# main_board.net
KiCad netlist of a schematic drawn in EAGLE
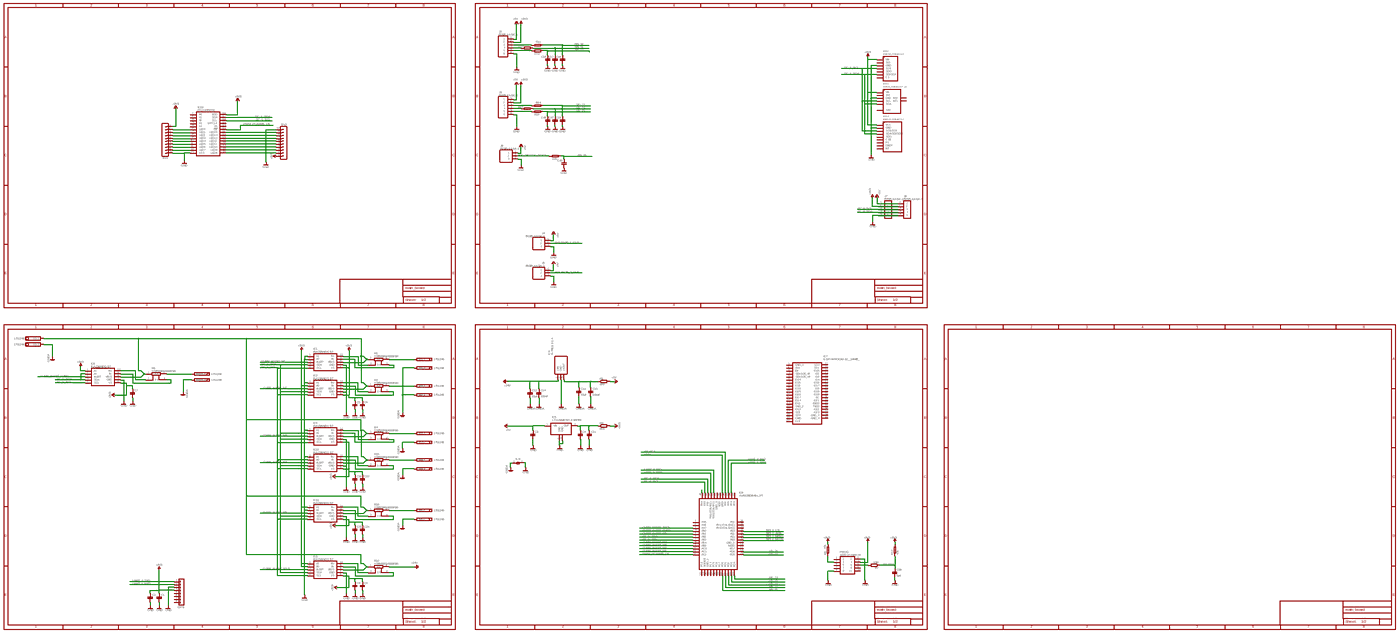
[diagram p0: schematic, sheet 1, overview]
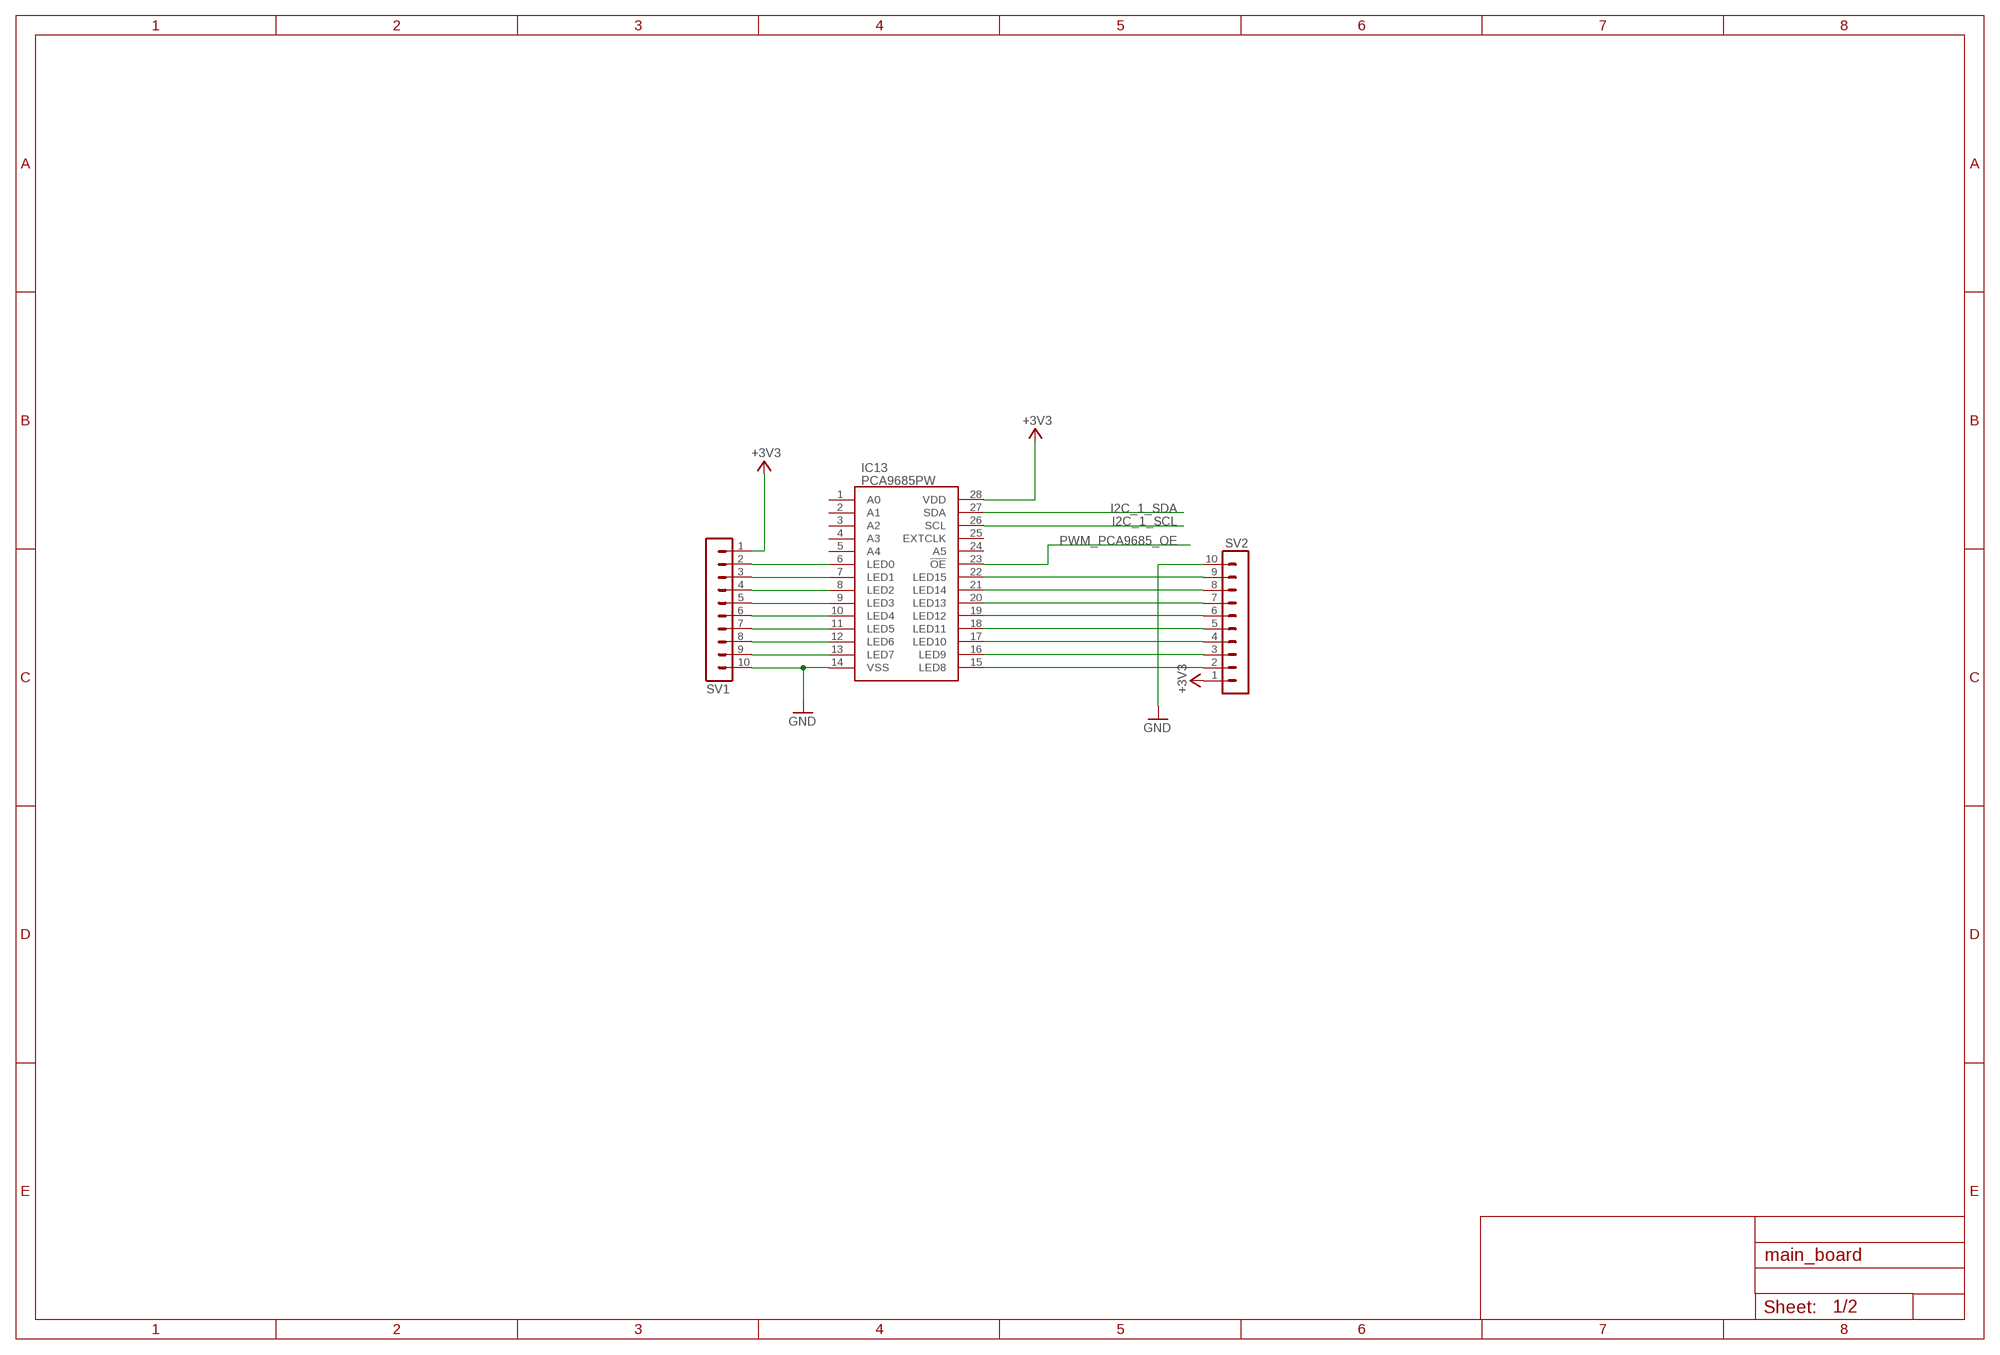
[diagram p1: schematic, sheet 1, part 1 of 7]
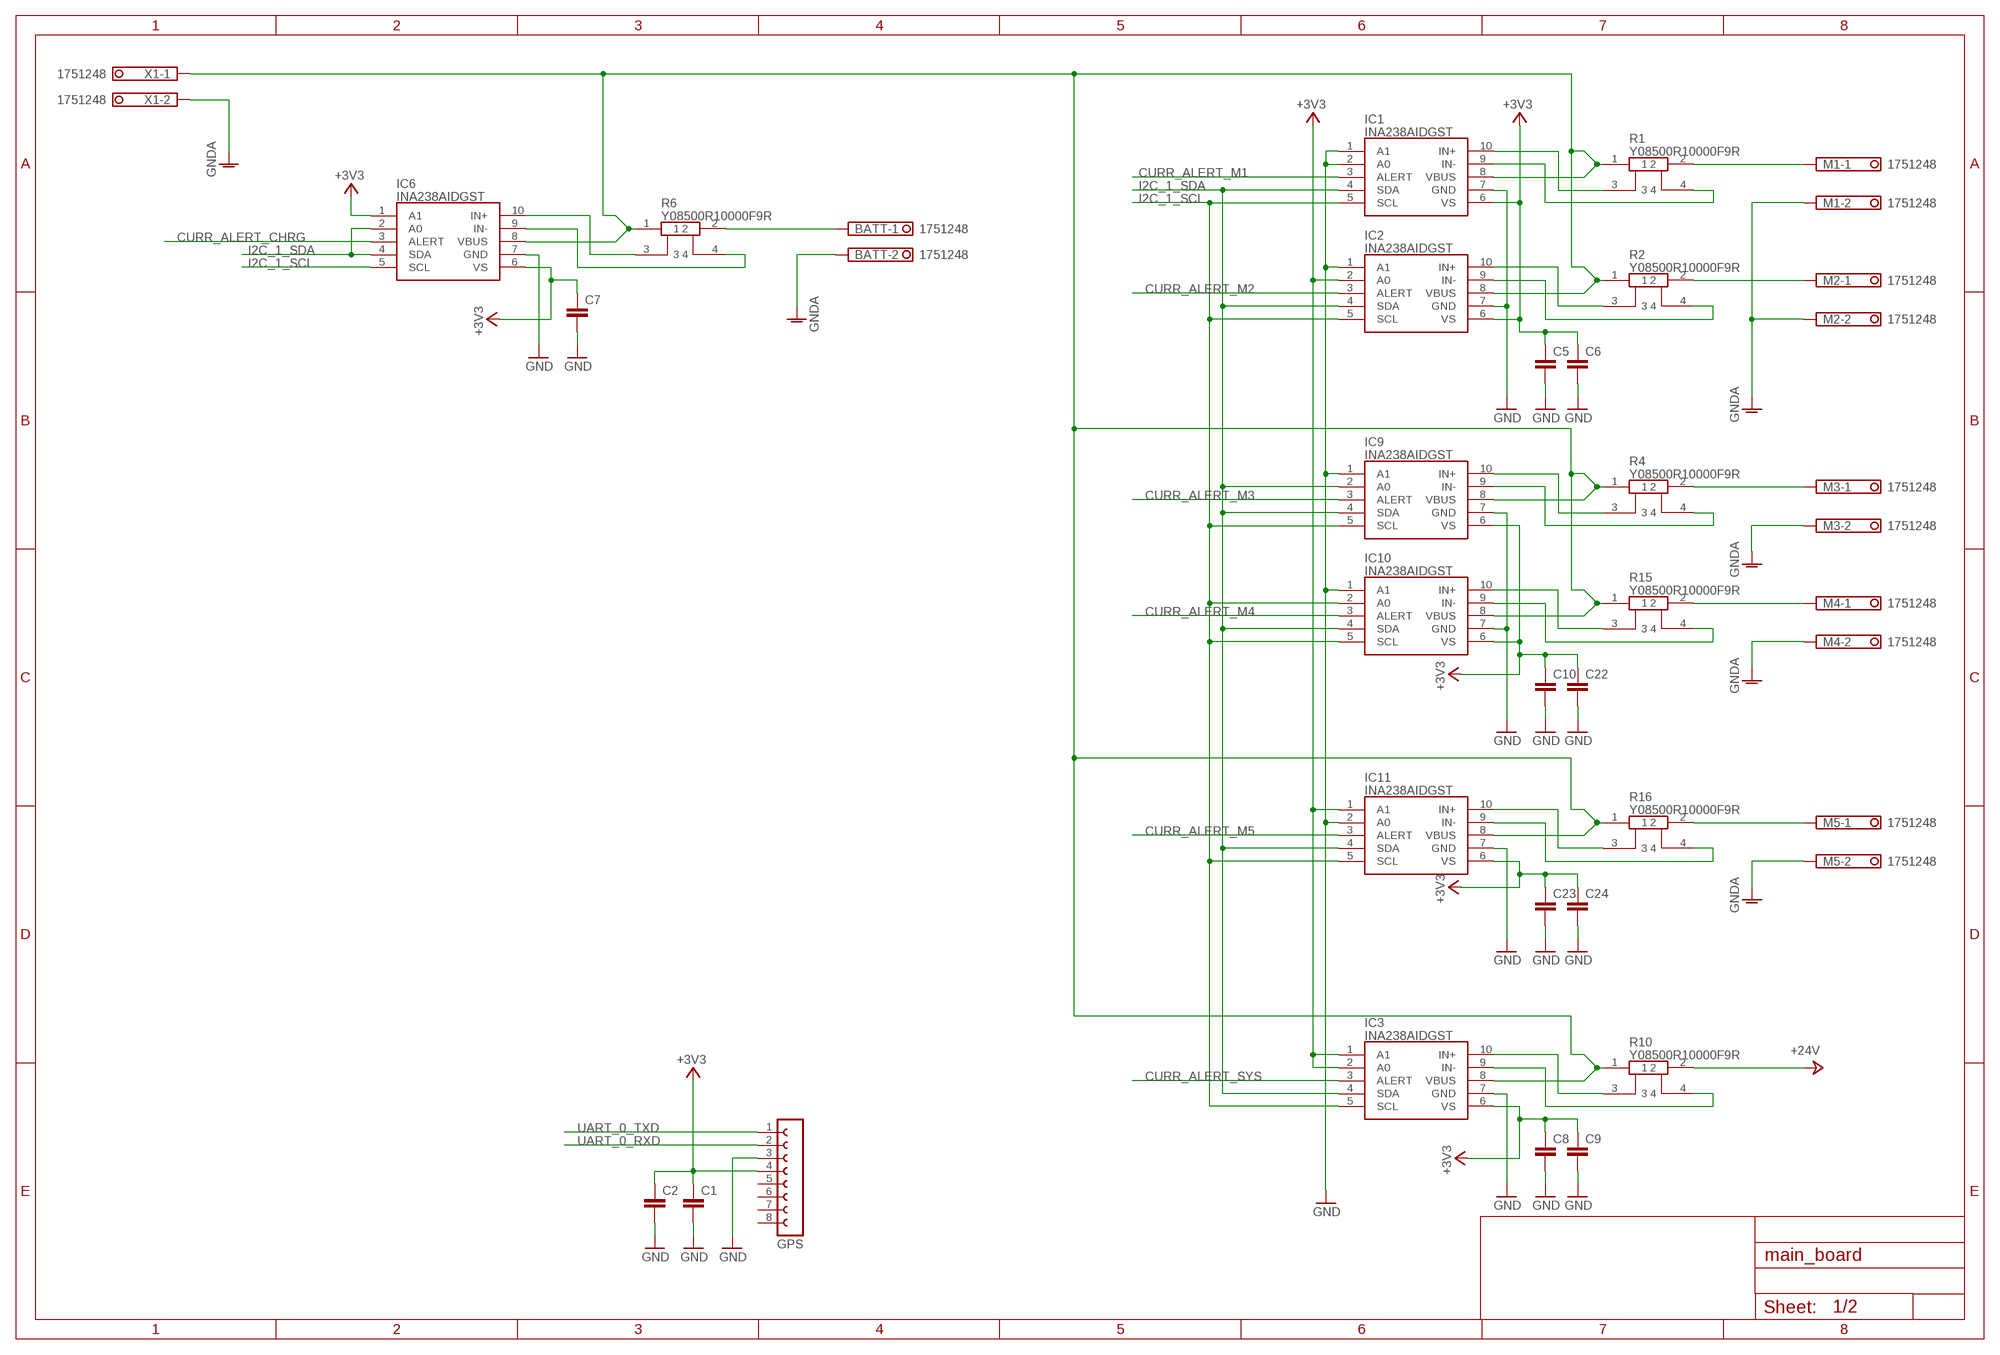
[diagram p2: schematic, sheet 1, part 2 of 7]
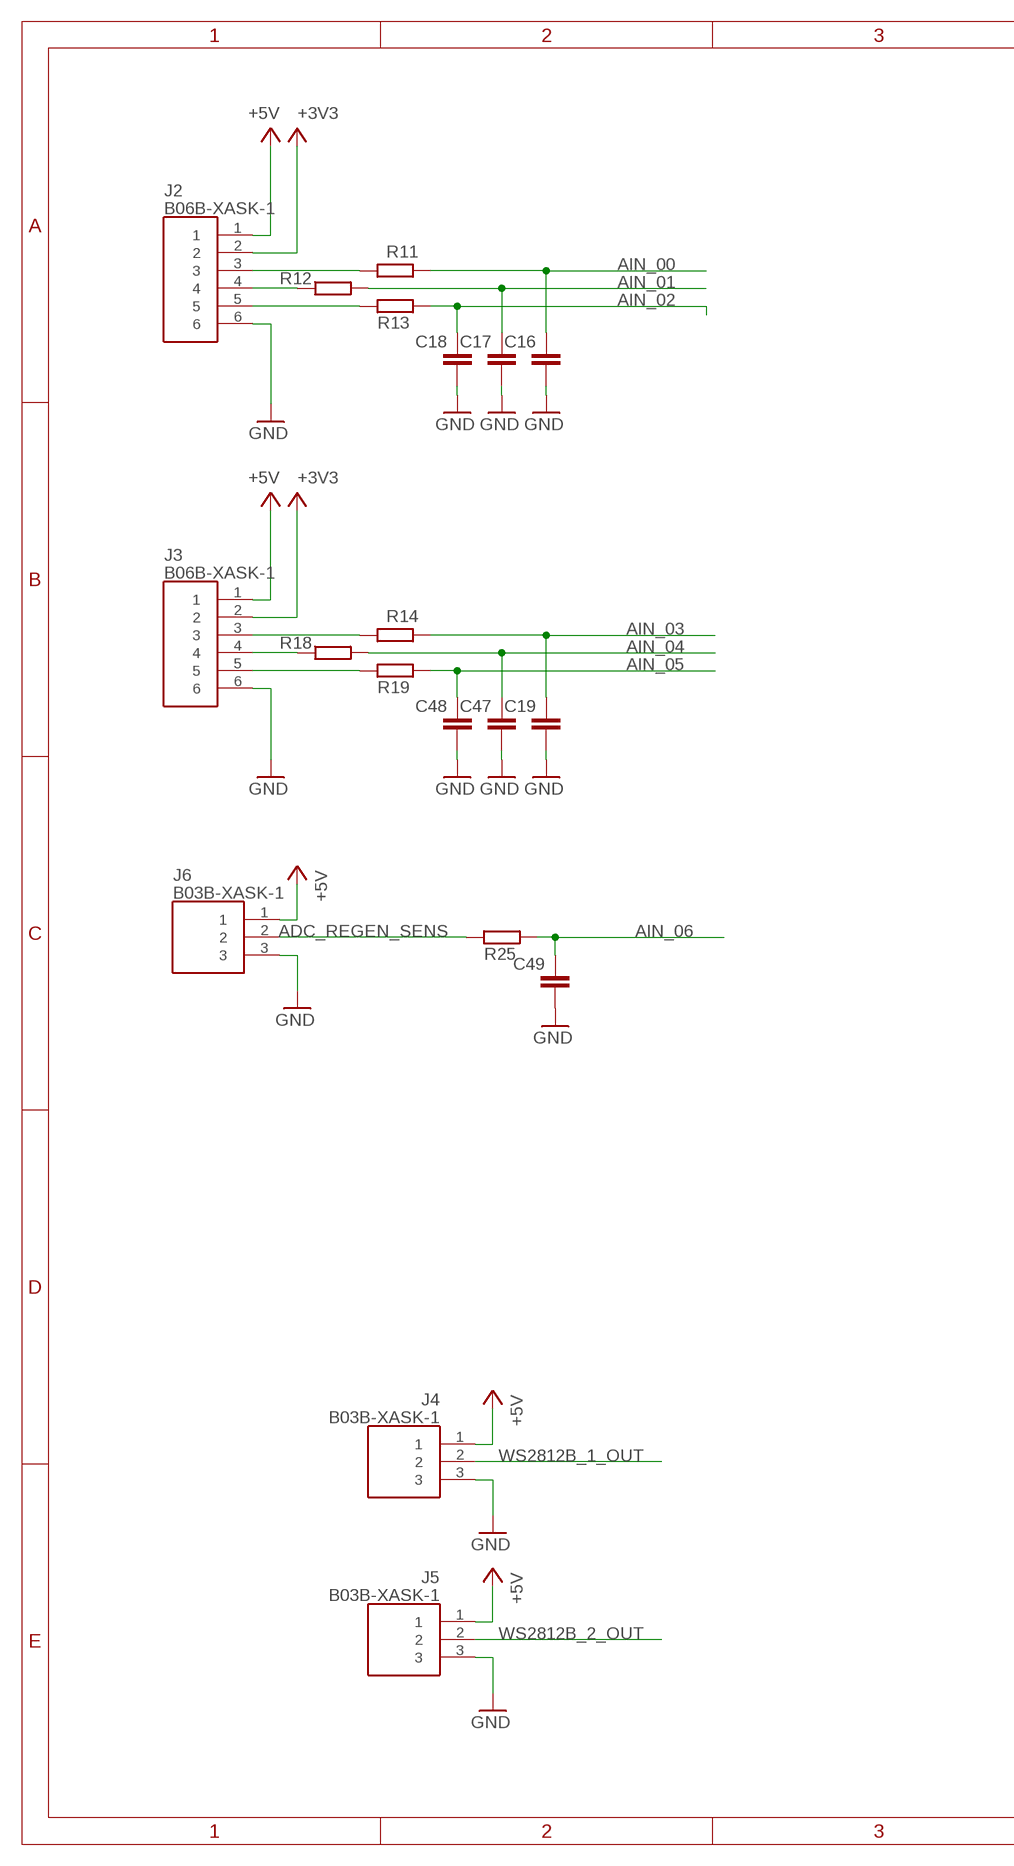
[diagram p3: schematic, sheet 1, part 3 of 7]
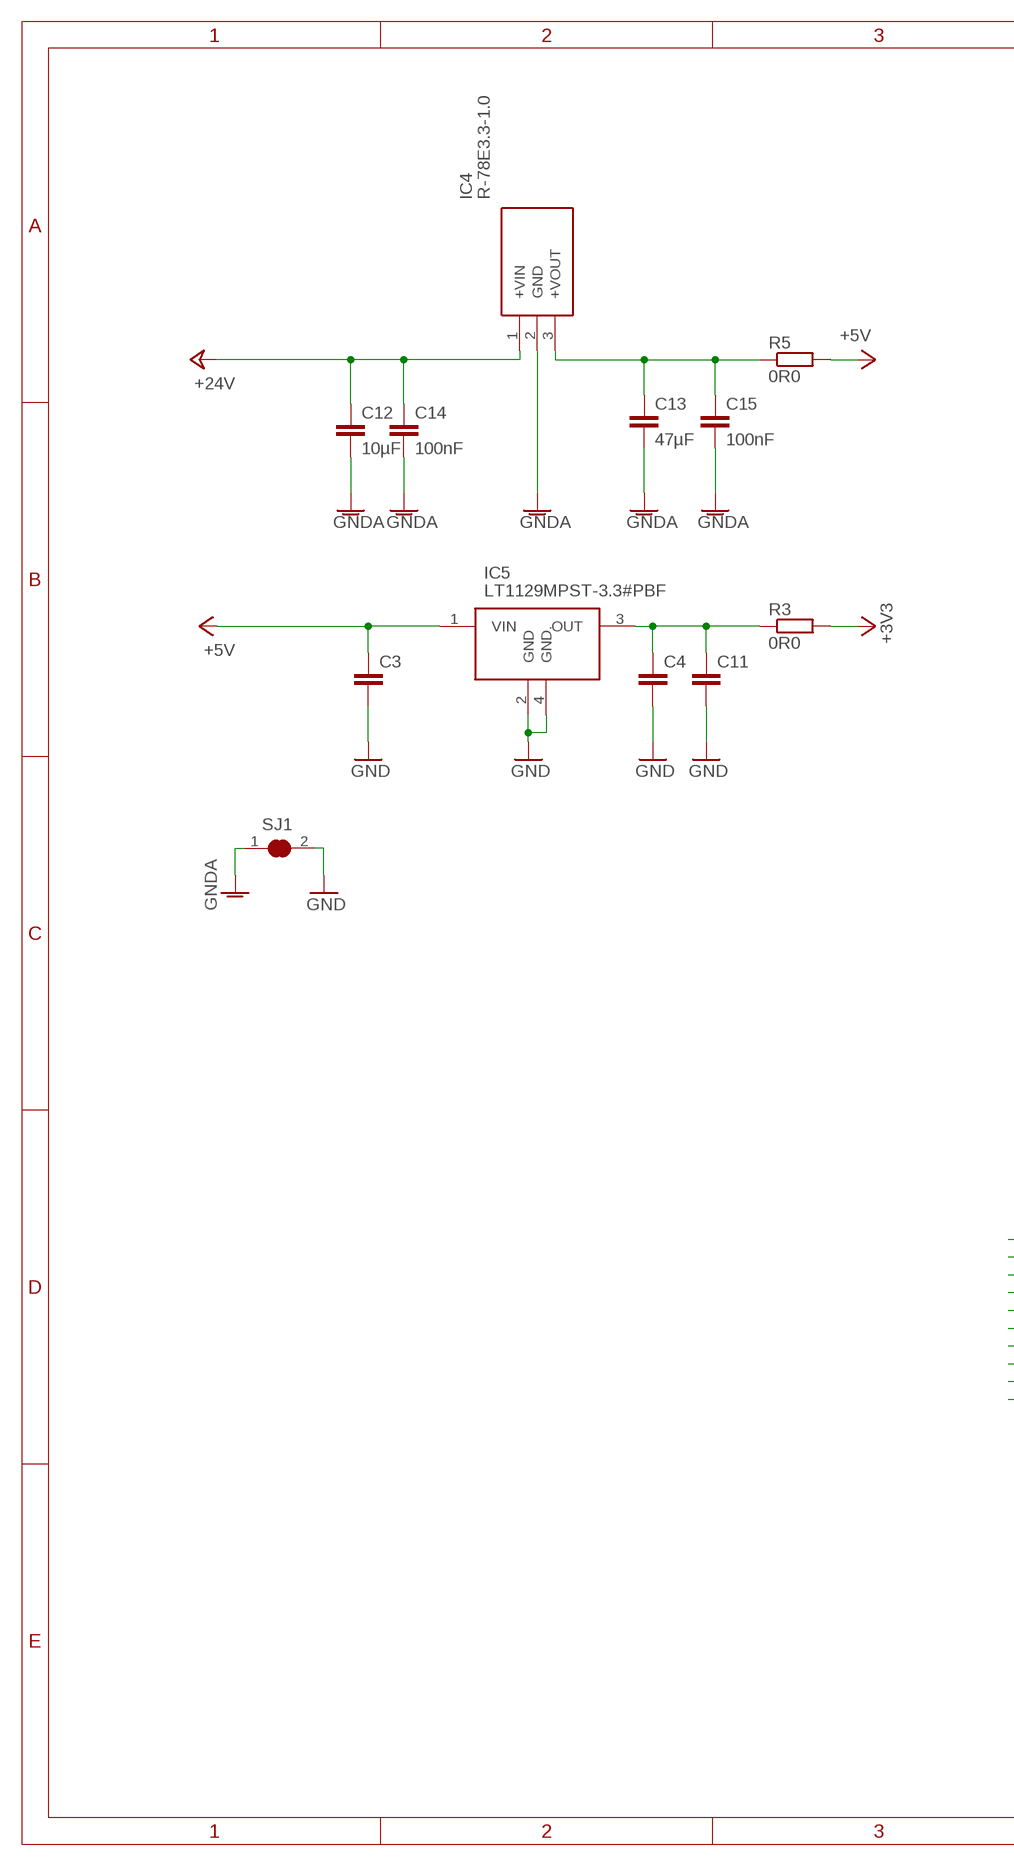
[diagram p4: schematic, sheet 1, part 4 of 7]
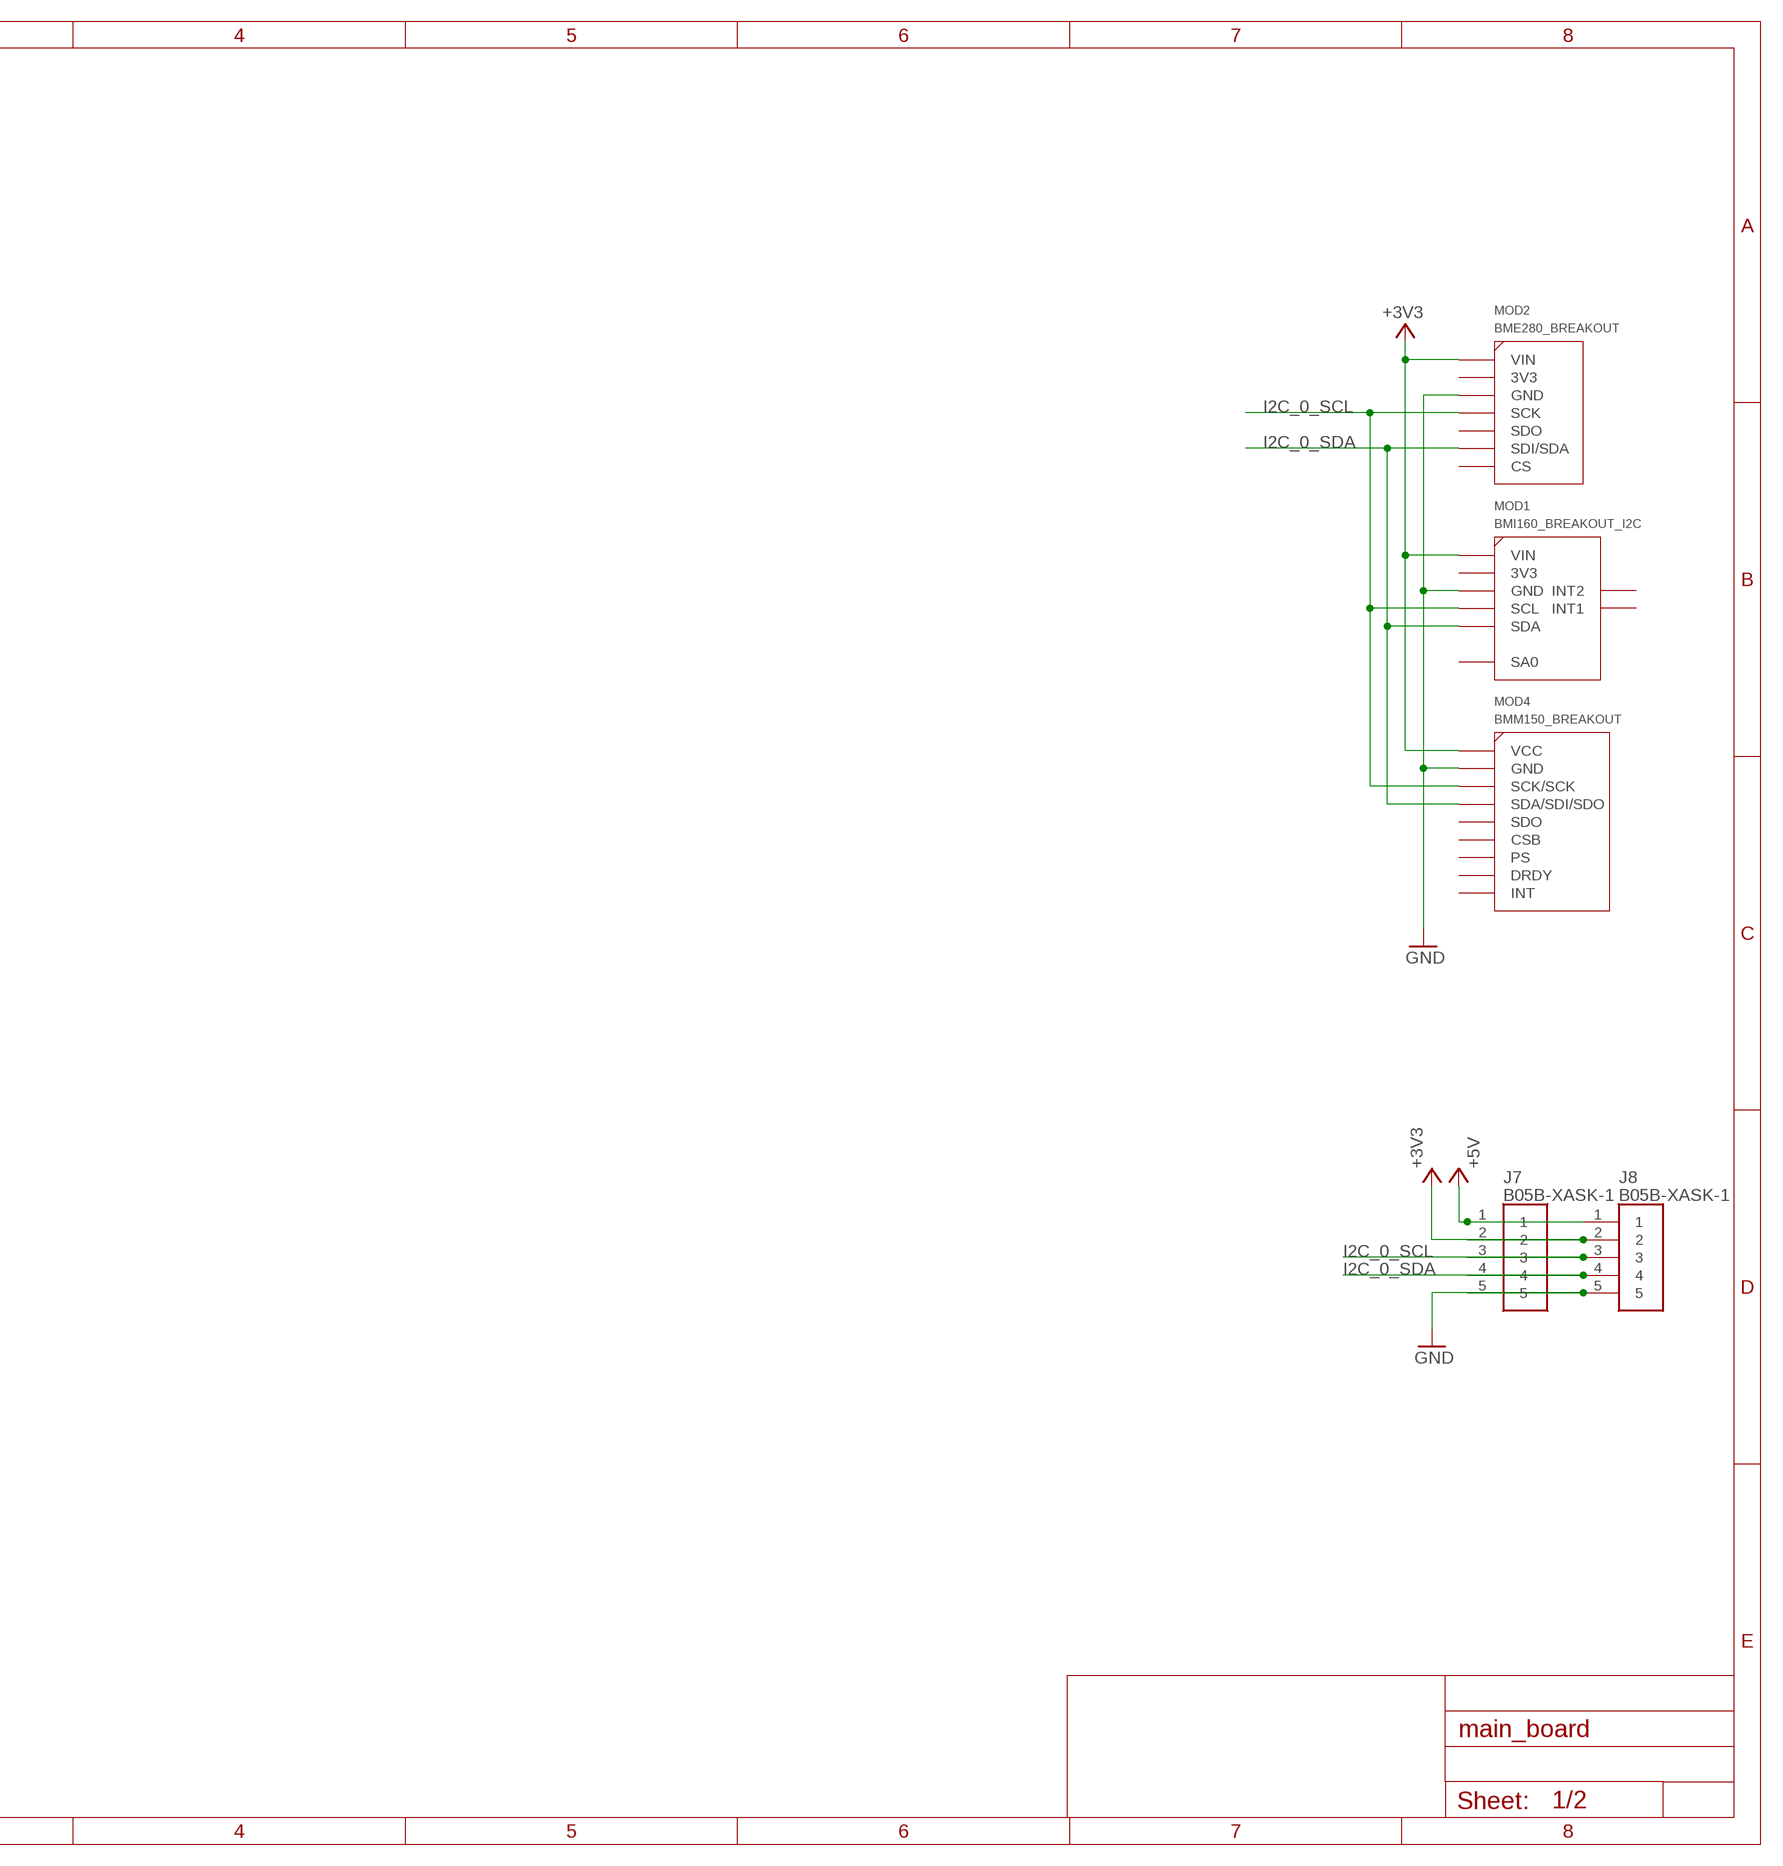
[diagram p5: schematic, sheet 1, part 5 of 7]
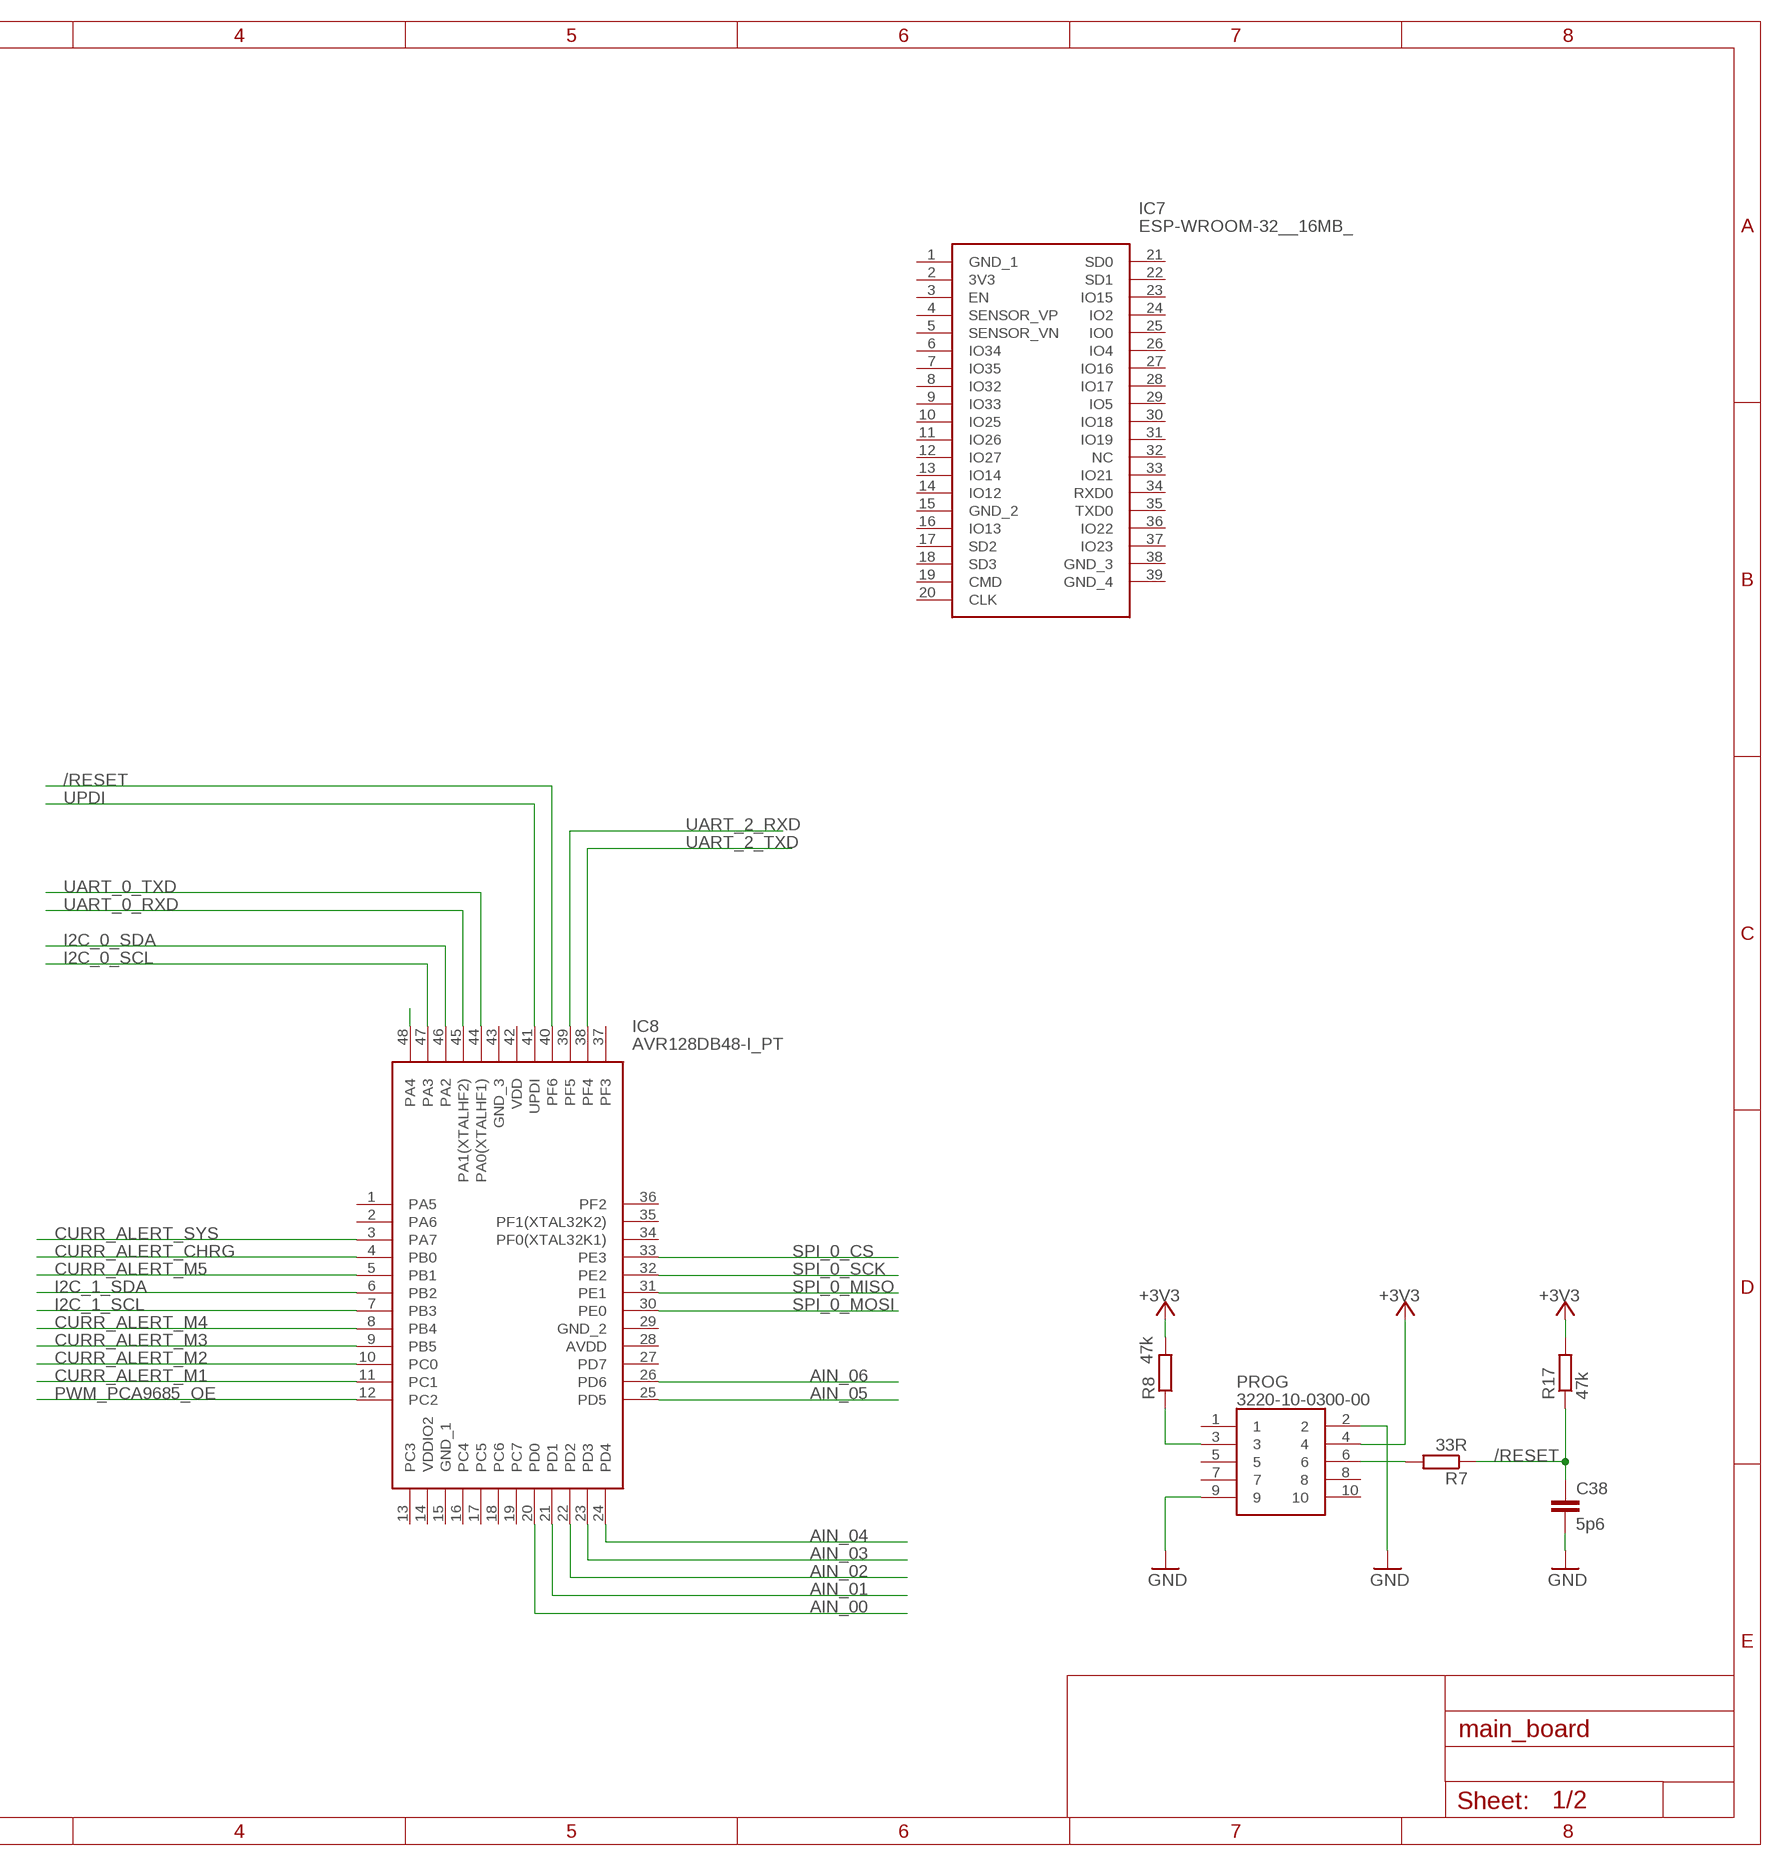
[diagram p6: schematic, sheet 1, part 6 of 7]
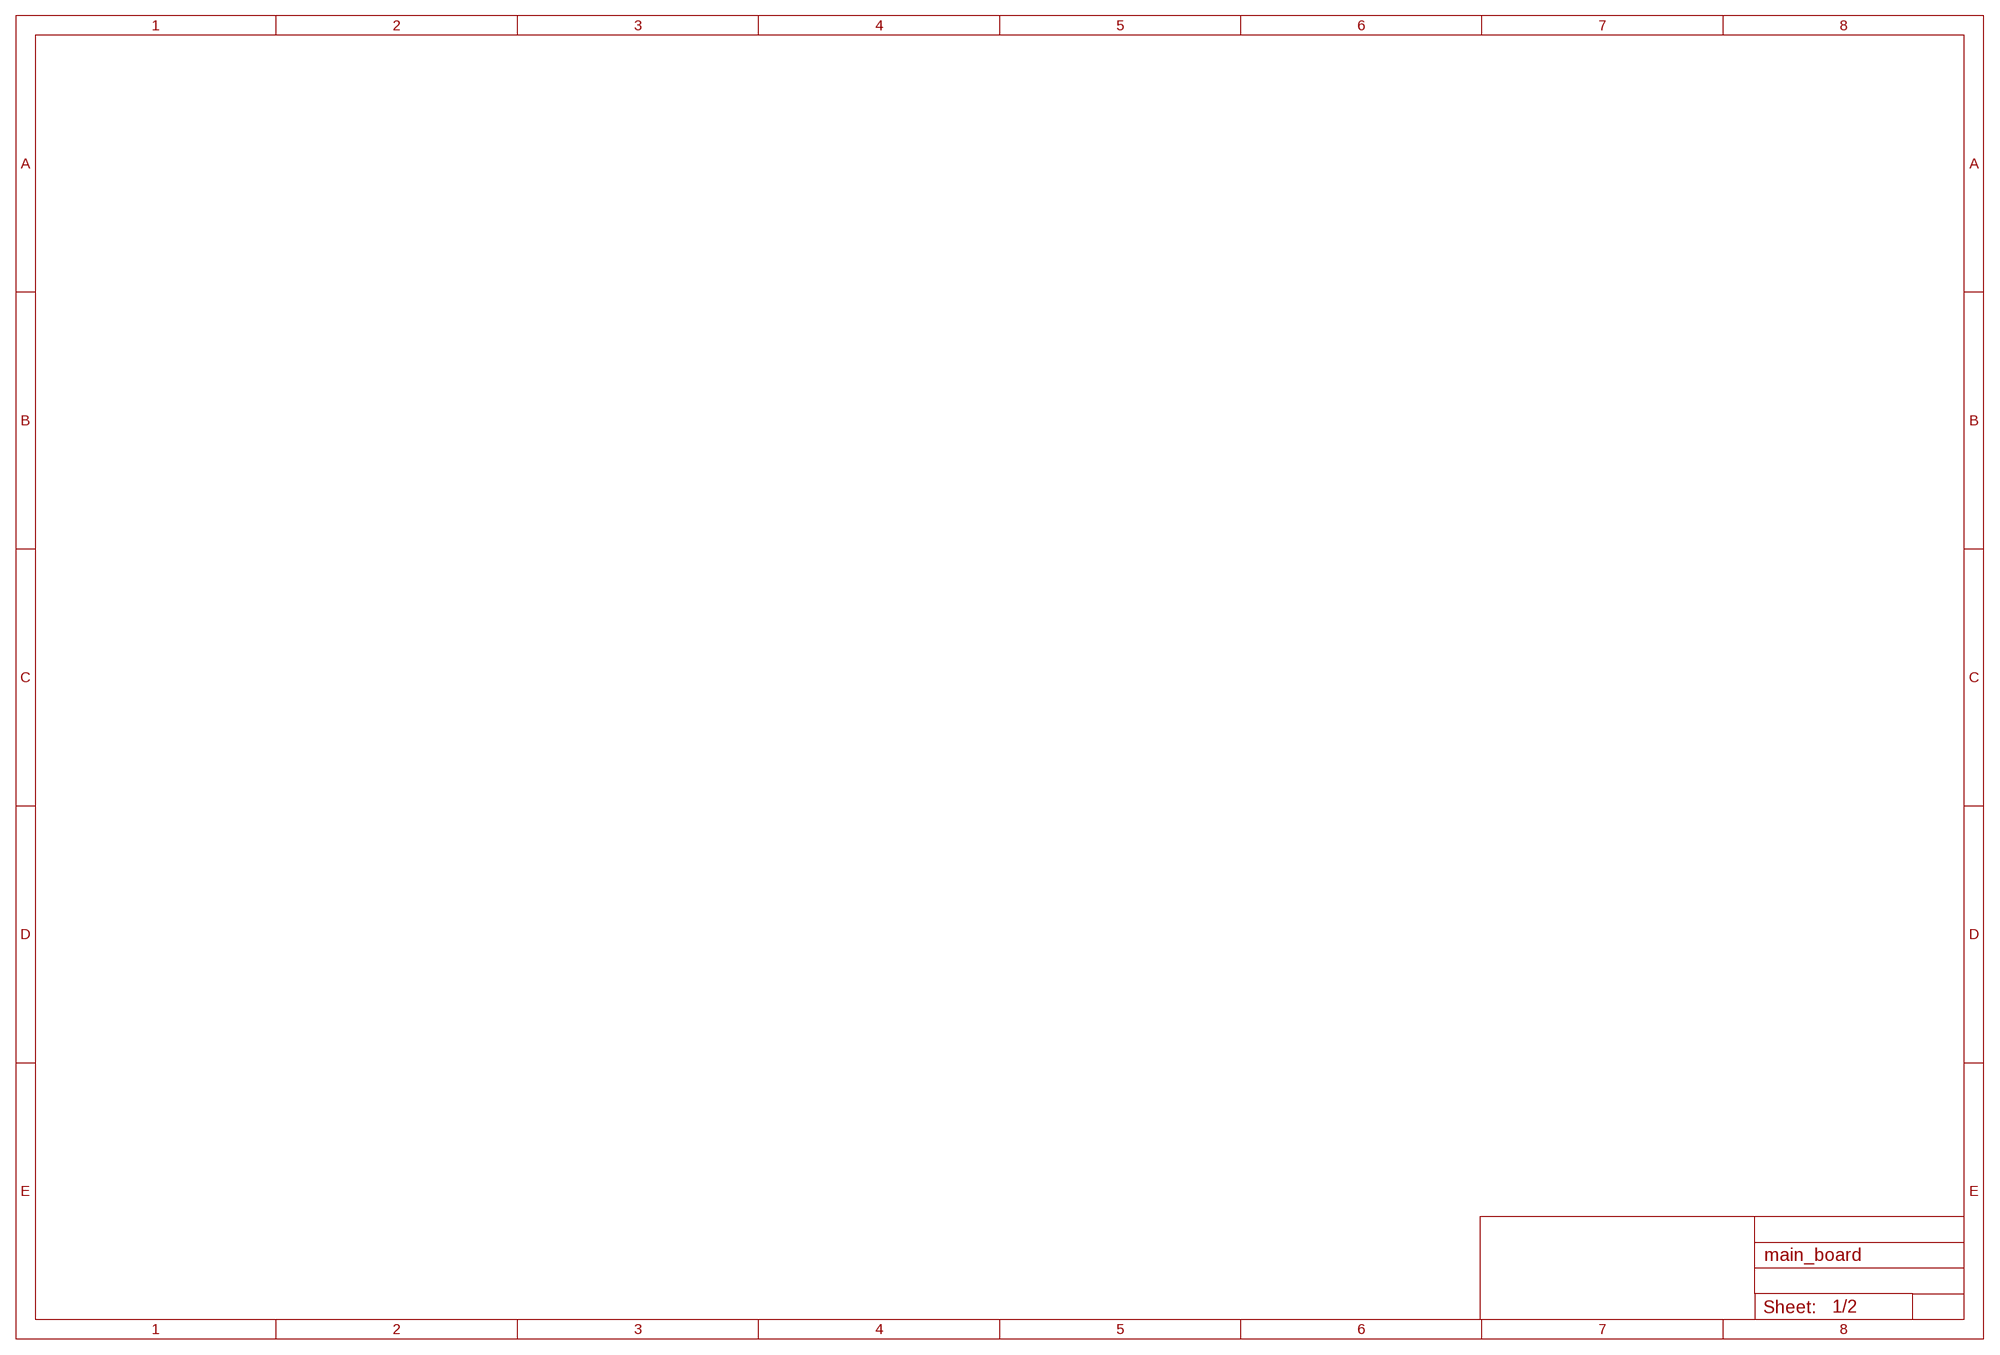
[diagram p7: schematic, sheet 1, part 7 of 7]
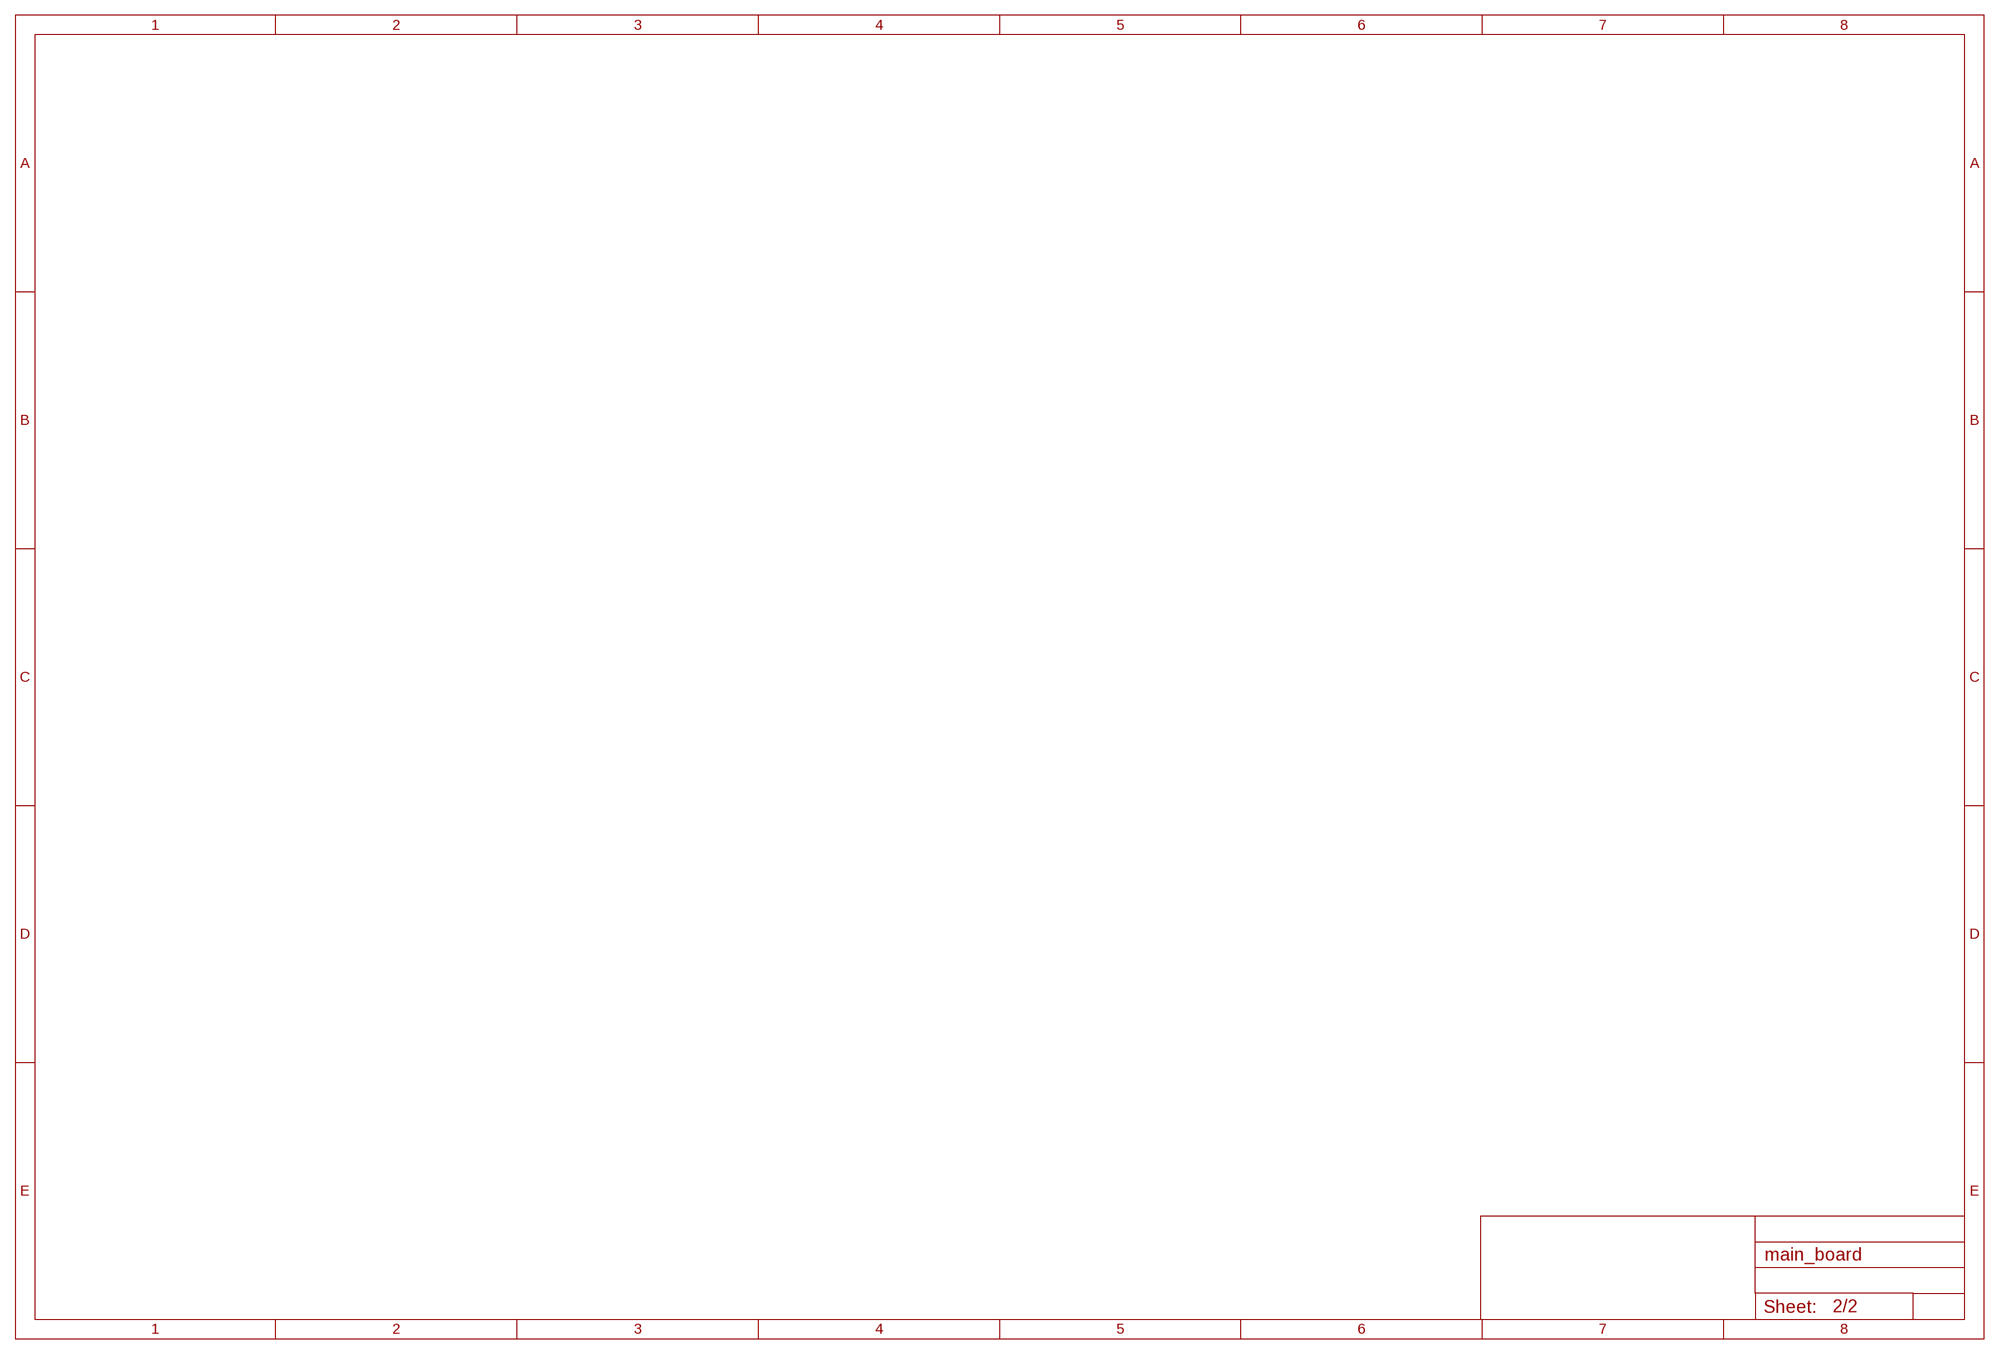
[diagram p8: schematic, sheet 2]

(export (version "E")
  (design (tool "Eeschema 10.0.6"))
  (components
    (comp (ref "BATT")
      (value "1751248")
      (footprint "eagle-import:1751248")
      (libsource (lib "eagle-import") (part "1751248"))
    )
    (comp (ref "C1")
      (value "C-EUC0603")
      (footprint "eagle-import:C0603")
      (libsource (lib "eagle-import") (part "C-EUC0603"))
    )
    (comp (ref "C2")
      (value "C-EUC0603")
      (footprint "eagle-import:C0603")
      (libsource (lib "eagle-import") (part "C-EUC0603"))
    )
    (comp (ref "C3")
      (value "C-EUC0603")
      (footprint "eagle-import:C0603")
      (libsource (lib "eagle-import") (part "C-EUC0603"))
    )
    (comp (ref "C4")
      (value "C-EUC0603")
      (footprint "eagle-import:C0603")
      (libsource (lib "eagle-import") (part "C-EUC0603"))
    )
    (comp (ref "C5")
      (value "C-EUC0603")
      (footprint "eagle-import:C0603")
      (libsource (lib "eagle-import") (part "C-EUC0603"))
    )
    (comp (ref "C6")
      (value "C-EUC0603")
      (footprint "eagle-import:C0603")
      (libsource (lib "eagle-import") (part "C-EUC0603"))
    )
    (comp (ref "C7")
      (value "C-EUC0603")
      (footprint "eagle-import:C0603")
      (libsource (lib "eagle-import") (part "C-EUC0603"))
    )
    (comp (ref "C8")
      (value "C-EUC0603")
      (footprint "eagle-import:C0603")
      (libsource (lib "eagle-import") (part "C-EUC0603"))
    )
    (comp (ref "C9")
      (value "C-EUC0603")
      (footprint "eagle-import:C0603")
      (libsource (lib "eagle-import") (part "C-EUC0603"))
    )
    (comp (ref "C10")
      (value "C-EUC0603")
      (footprint "eagle-import:C0603")
      (libsource (lib "eagle-import") (part "C-EUC0603"))
    )
    (comp (ref "C11")
      (value "C-EUC0603")
      (footprint "eagle-import:C0603")
      (libsource (lib "eagle-import") (part "C-EUC0603"))
    )
    (comp (ref "C12")
      (value "10µF")
      (footprint "eagle-import:C1210")
      (libsource (lib "eagle-import") (part "C-EUC1210"))
    )
    (comp (ref "C13")
      (value "47µF")
      (footprint "eagle-import:C1210")
      (libsource (lib "eagle-import") (part "C-EUC1210"))
    )
    (comp (ref "C14")
      (value "100nF")
      (footprint "eagle-import:C0603")
      (libsource (lib "eagle-import") (part "C-EUC0603"))
    )
    (comp (ref "C15")
      (value "100nF")
      (footprint "eagle-import:C0603")
      (libsource (lib "eagle-import") (part "C-EUC0603"))
    )
    (comp (ref "C16")
      (value "C-EUC0603")
      (footprint "eagle-import:C0603")
      (libsource (lib "eagle-import") (part "C-EUC0603"))
    )
    (comp (ref "C17")
      (value "C-EUC0603")
      (footprint "eagle-import:C0603")
      (libsource (lib "eagle-import") (part "C-EUC0603"))
    )
    (comp (ref "C18")
      (value "C-EUC0603")
      (footprint "eagle-import:C0603")
      (libsource (lib "eagle-import") (part "C-EUC0603"))
    )
    (comp (ref "C19")
      (value "C-EUC0603")
      (footprint "eagle-import:C0603")
      (libsource (lib "eagle-import") (part "C-EUC0603"))
    )
    (comp (ref "C22")
      (value "C-EUC0603")
      (footprint "eagle-import:C0603")
      (libsource (lib "eagle-import") (part "C-EUC0603"))
    )
    (comp (ref "C23")
      (value "C-EUC0603")
      (footprint "eagle-import:C0603")
      (libsource (lib "eagle-import") (part "C-EUC0603"))
    )
    (comp (ref "C24")
      (value "C-EUC0603")
      (footprint "eagle-import:C0603")
      (libsource (lib "eagle-import") (part "C-EUC0603"))
    )
    (comp (ref "C38")
      (value "5p6")
      (footprint "eagle-import:C0603")
      (libsource (lib "eagle-import") (part "C-EUC0603"))
    )
    (comp (ref "C47")
      (value "C-EUC0603")
      (footprint "eagle-import:C0603")
      (libsource (lib "eagle-import") (part "C-EUC0603"))
    )
    (comp (ref "C48")
      (value "C-EUC0603")
      (footprint "eagle-import:C0603")
      (libsource (lib "eagle-import") (part "C-EUC0603"))
    )
    (comp (ref "C49")
      (value "C-EUC0603")
      (footprint "eagle-import:C0603")
      (libsource (lib "eagle-import") (part "C-EUC0603"))
    )
    (comp (ref "GPS")
      (value "FE08-1")
      (footprint "eagle-import:FE08")
      (libsource (lib "eagle-import") (part "FE08-1"))
    )
    (comp (ref "IC1")
      (value "INA238AIDGST")
      (footprint "eagle-import:SOP50P490X110-10N")
      (fields (field (name "MOUSER_PART_NUMBER") "595-INA238AIDGST"))
      (libsource (lib "eagle-import") (part "INA238AIDGST"))
    )
    (comp (ref "IC2")
      (value "INA238AIDGST")
      (footprint "eagle-import:SOP50P490X110-10N")
      (fields (field (name "MOUSER_PART_NUMBER") "595-INA238AIDGST"))
      (libsource (lib "eagle-import") (part "INA238AIDGST"))
    )
    (comp (ref "IC3")
      (value "INA238AIDGST")
      (footprint "eagle-import:SOP50P490X110-10N")
      (fields (field (name "MOUSER_PART_NUMBER") "595-INA238AIDGST"))
      (libsource (lib "eagle-import") (part "INA238AIDGST"))
    )
    (comp (ref "IC4")
      (value "R-78E3.3-1.0")
      (footprint "eagle-import:R78E3310")
      (fields (field (name "MOUSER_PART_NUMBER") "919-R-78E3.3-1.0"))
      (libsource (lib "eagle-import") (part "R-78E3.3-1.0"))
    )
    (comp (ref "IC5")
      (value "LT1129MPST-3.3#PBF")
      (footprint "eagle-import:SOT230P700X180-4N")
      (fields (field (name "MOUSER_PART_NUMBER") "584-1129MPST-3.3PBF"))
      (libsource (lib "eagle-import") (part "LT1129MPST-3.3#PBF"))
    )
    (comp (ref "IC6")
      (value "INA238AIDGST")
      (footprint "eagle-import:SOP50P490X110-10N")
      (fields (field (name "MOUSER_PART_NUMBER") "595-INA238AIDGST"))
      (libsource (lib "eagle-import") (part "INA238AIDGST"))
    )
    (comp (ref "IC7")
      (value "ESP-WROOM-32__16MB_")
      (footprint "eagle-import:ESP32WROOM32D")
      (fields
        (field (name "ARROW_PART_NUMBER") "ESP-WROOM-32 (16MB)")
        (field (name "MOUSER_PART_NUMBER") "356-ESPWROOM3216MB")
      )
      (libsource (lib "eagle-import") (part "ESP-WROOM-32__16MB_"))
    )
    (comp (ref "IC8")
      (value "AVR128DB48-I_PT")
      (footprint "eagle-import:QFP50P900X900X120-48N")
      (fields
        (field (name "ARROW_PART_NUMBER") "AVR128DB48-I/PT")
        (field (name "MOUSER_PART_NUMBER") "579-AVR128DB48-I/PT")
      )
      (libsource (lib "eagle-import") (part "AVR128DB48-I_PT"))
    )
    (comp (ref "IC9")
      (value "INA238AIDGST")
      (footprint "eagle-import:SOP50P490X110-10N")
      (fields (field (name "MOUSER_PART_NUMBER") "595-INA238AIDGST"))
      (libsource (lib "eagle-import") (part "INA238AIDGST"))
    )
    (comp (ref "IC10")
      (value "INA238AIDGST")
      (footprint "eagle-import:SOP50P490X110-10N")
      (fields (field (name "MOUSER_PART_NUMBER") "595-INA238AIDGST"))
      (libsource (lib "eagle-import") (part "INA238AIDGST"))
    )
    (comp (ref "IC11")
      (value "INA238AIDGST")
      (footprint "eagle-import:SOP50P490X110-10N")
      (fields (field (name "MOUSER_PART_NUMBER") "595-INA238AIDGST"))
      (libsource (lib "eagle-import") (part "INA238AIDGST"))
    )
    (comp (ref "IC13")
      (value "PCA9685PW")
      (footprint "eagle-import:SOP65P640X110-28N")
      (libsource (lib "eagle-import") (part "PCA9685PW"))
    )
    (comp (ref "J2")
      (value "B06B-XASK-1")
      (footprint "eagle-import:SHDR6W60P0X250_1X6_1750X640X88")
      (fields (field (name "ARROW_PART_NUMBER") "B06B-XASK-1 (LF)(SN)"))
      (libsource (lib "eagle-import") (part "B06B-XASK-1"))
    )
    (comp (ref "J3")
      (value "B06B-XASK-1")
      (footprint "eagle-import:SHDR6W60P0X250_1X6_1750X640X88")
      (fields (field (name "ARROW_PART_NUMBER") "B06B-XASK-1 (LF)(SN)"))
      (libsource (lib "eagle-import") (part "B06B-XASK-1"))
    )
    (comp (ref "J4")
      (value "B03B-XASK-1")
      (footprint "eagle-import:SHDR3W60P0X250_1X3_1000X640X88")
      (fields (field (name "MANUFACTURER_PART_NUMBER") "B03B-XASK-1 (LF)(SN)"))
      (libsource (lib "eagle-import") (part "B03B-XASK-1"))
    )
    (comp (ref "J5")
      (value "B03B-XASK-1")
      (footprint "eagle-import:SHDR3W60P0X250_1X3_1000X640X88")
      (fields (field (name "MANUFACTURER_PART_NUMBER") "B03B-XASK-1 (LF)(SN)"))
      (libsource (lib "eagle-import") (part "B03B-XASK-1"))
    )
    (comp (ref "J6")
      (value "B03B-XASK-1")
      (footprint "eagle-import:SHDR3W60P0X250_1X3_1000X640X88")
      (fields (field (name "MANUFACTURER_PART_NUMBER") "B03B-XASK-1 (LF)(SN)"))
      (libsource (lib "eagle-import") (part "B03B-XASK-1"))
    )
    (comp (ref "J7")
      (value "B05B-XASK-1")
      (footprint "eagle-import:SHDR5W60P0X250_1X5_1500X640X88")
      (fields (field (name "MANUFACTURER_PART_NUMBER") "B05B-XASK-1 (LF)(SN)"))
      (libsource (lib "eagle-import") (part "B05B-XASK-1"))
    )
    (comp (ref "J8")
      (value "B05B-XASK-1")
      (footprint "eagle-import:SHDR5W60P0X250_1X5_1500X640X88")
      (fields (field (name "MANUFACTURER_PART_NUMBER") "B05B-XASK-1 (LF)(SN)"))
      (libsource (lib "eagle-import") (part "B05B-XASK-1"))
    )
    (comp (ref "M1")
      (value "1751248")
      (footprint "eagle-import:1751248")
      (libsource (lib "eagle-import") (part "1751248"))
    )
    (comp (ref "M2")
      (value "1751248")
      (footprint "eagle-import:1751248")
      (libsource (lib "eagle-import") (part "1751248"))
    )
    (comp (ref "M3")
      (value "1751248")
      (footprint "eagle-import:1751248")
      (libsource (lib "eagle-import") (part "1751248"))
    )
    (comp (ref "M4")
      (value "1751248")
      (footprint "eagle-import:1751248")
      (libsource (lib "eagle-import") (part "1751248"))
    )
    (comp (ref "M5")
      (value "1751248")
      (footprint "eagle-import:1751248")
      (libsource (lib "eagle-import") (part "1751248"))
    )
    (comp (ref "MOD1")
      (value "BMI160_BREAKOUT_I2C")
      (footprint "eagle-import:BMI160_BREAKOUT_I2C")
      (libsource (lib "eagle-import") (part "BMI160_BREAKOUT_I2C"))
    )
    (comp (ref "MOD2")
      (value "BME280_BREAKOUT")
      (footprint "eagle-import:BME280_BREAKOUT")
      (libsource (lib "eagle-import") (part "BME280_BREAKOUT"))
    )
    (comp (ref "MOD4")
      (value "BMM150_BREAKOUT")
      (footprint "eagle-import:BMM150_BREAKOUT")
      (libsource (lib "eagle-import") (part "BMM150_BREAKOUT"))
    )
    (comp (ref "PROG")
      (value "3220-10-0300-00")
      (footprint "eagle-import:3220-10-0300-00")
      (libsource (lib "eagle-import") (part "3220-10-0300-00"))
    )
    (comp (ref "R1")
      (value "Y08500R10000F9R")
      (footprint "eagle-import:Y08500R10000F9R")
      (fields (field (name "MOUSER_PART_NUMBER") "71-VCS16250R1000FST"))
      (libsource (lib "eagle-import") (part "Y08500R10000F9R"))
    )
    (comp (ref "R2")
      (value "Y08500R10000F9R")
      (footprint "eagle-import:Y08500R10000F9R")
      (fields (field (name "MOUSER_PART_NUMBER") "71-VCS16250R1000FST"))
      (libsource (lib "eagle-import") (part "Y08500R10000F9R"))
    )
    (comp (ref "R3")
      (value "0R0")
      (footprint "eagle-import:R0603")
      (libsource (lib "eagle-import") (part "R-EU_R0603"))
    )
    (comp (ref "R4")
      (value "Y08500R10000F9R")
      (footprint "eagle-import:Y08500R10000F9R")
      (fields (field (name "MOUSER_PART_NUMBER") "71-VCS16250R1000FST"))
      (libsource (lib "eagle-import") (part "Y08500R10000F9R"))
    )
    (comp (ref "R5")
      (value "0R0")
      (footprint "eagle-import:R0603")
      (libsource (lib "eagle-import") (part "R-EU_R0603"))
    )
    (comp (ref "R6")
      (value "Y08500R10000F9R")
      (footprint "eagle-import:Y08500R10000F9R")
      (fields (field (name "MOUSER_PART_NUMBER") "71-VCS16250R1000FST"))
      (libsource (lib "eagle-import") (part "Y08500R10000F9R"))
    )
    (comp (ref "R7")
      (value "33R")
      (footprint "eagle-import:R0603")
      (libsource (lib "eagle-import") (part "R-EU_R0603"))
    )
    (comp (ref "R8")
      (value "47k")
      (footprint "eagle-import:R0603")
      (libsource (lib "eagle-import") (part "R-EU_R0603"))
    )
    (comp (ref "R10")
      (value "Y08500R10000F9R")
      (footprint "eagle-import:Y08500R10000F9R")
      (fields (field (name "MOUSER_PART_NUMBER") "71-VCS16250R1000FST"))
      (libsource (lib "eagle-import") (part "Y08500R10000F9R"))
    )
    (comp (ref "R11")
      (value "R-EU_R0603")
      (footprint "eagle-import:R0603")
      (libsource (lib "eagle-import") (part "R-EU_R0603"))
    )
    (comp (ref "R12")
      (value "R-EU_R0603")
      (footprint "eagle-import:R0603")
      (libsource (lib "eagle-import") (part "R-EU_R0603"))
    )
    (comp (ref "R13")
      (value "R-EU_R0603")
      (footprint "eagle-import:R0603")
      (libsource (lib "eagle-import") (part "R-EU_R0603"))
    )
    (comp (ref "R14")
      (value "R-EU_R0603")
      (footprint "eagle-import:R0603")
      (libsource (lib "eagle-import") (part "R-EU_R0603"))
    )
    (comp (ref "R15")
      (value "Y08500R10000F9R")
      (footprint "eagle-import:Y08500R10000F9R")
      (fields (field (name "MOUSER_PART_NUMBER") "71-VCS16250R1000FST"))
      (libsource (lib "eagle-import") (part "Y08500R10000F9R"))
    )
    (comp (ref "R16")
      (value "Y08500R10000F9R")
      (footprint "eagle-import:Y08500R10000F9R")
      (fields (field (name "MOUSER_PART_NUMBER") "71-VCS16250R1000FST"))
      (libsource (lib "eagle-import") (part "Y08500R10000F9R"))
    )
    (comp (ref "R17")
      (value "47k")
      (footprint "eagle-import:R0603")
      (libsource (lib "eagle-import") (part "R-EU_R0603"))
    )
    (comp (ref "R18")
      (value "R-EU_R0603")
      (footprint "eagle-import:R0603")
      (libsource (lib "eagle-import") (part "R-EU_R0603"))
    )
    (comp (ref "R19")
      (value "R-EU_R0603")
      (footprint "eagle-import:R0603")
      (libsource (lib "eagle-import") (part "R-EU_R0603"))
    )
    (comp (ref "R25")
      (value "R-EU_R0603")
      (footprint "eagle-import:R0603")
      (libsource (lib "eagle-import") (part "R-EU_R0603"))
    )
    (comp (ref "SJ1")
      (value "SOLDERJUMPER_CLOSEDPERM")
      (footprint "eagle-import:SOLDERJUMPER_CLOSEDPERM")
      (libsource (lib "eagle-import") (part "SOLDERJUMPER_CLOSEDPERM"))
    )
    (comp (ref "SV1")
      (value "MA10-1")
      (footprint "eagle-import:MA10-1")
      (libsource (lib "eagle-import") (part "MA10-1"))
    )
    (comp (ref "SV2")
      (value "MA10-1")
      (footprint "eagle-import:MA10-1")
      (libsource (lib "eagle-import") (part "MA10-1"))
    )
    (comp (ref "X1")
      (value "1751248")
      (footprint "eagle-import:1751248")
      (libsource (lib "eagle-import") (part "1751248"))
    )
  )
  (nets
    (net (code "1") (name "+3V3") (class "Default")
      (node (ref "C1") (pin "1") (pinfunction "1_1") (pintype "passive"))
      (node (ref "C10") (pin "1") (pinfunction "1_1") (pintype "passive"))
      (node (ref "C2") (pin "1") (pinfunction "1_1") (pintype "passive"))
      (node (ref "C22") (pin "1") (pinfunction "1_1") (pintype "passive"))
      (node (ref "C23") (pin "1") (pinfunction "1_1") (pintype "passive"))
      (node (ref "C24") (pin "1") (pinfunction "1_1") (pintype "passive"))
      (node (ref "C5") (pin "1") (pinfunction "1_1") (pintype "passive"))
      (node (ref "C6") (pin "1") (pinfunction "1_1") (pintype "passive"))
      (node (ref "C7") (pin "1") (pinfunction "1_1") (pintype "passive"))
      (node (ref "C8") (pin "1") (pinfunction "1_1") (pintype "passive"))
      (node (ref "C9") (pin "1") (pinfunction "1_1") (pintype "passive"))
      (node (ref "GPS") (pin "4") (pinfunction "4_4") (pintype "passive"))
      (node (ref "IC1") (pin "6") (pinfunction "VS_6") (pintype "bidirectional"))
      (node (ref "IC10") (pin "6") (pinfunction "VS_6") (pintype "bidirectional"))
      (node (ref "IC11") (pin "1") (pinfunction "A1_1") (pintype "bidirectional"))
      (node (ref "IC11") (pin "6") (pinfunction "VS_6") (pintype "bidirectional"))
      (node (ref "IC13") (pin "28") (pinfunction "VDD_28") (pintype "bidirectional"))
      (node (ref "IC2") (pin "2") (pinfunction "A0_2") (pintype "bidirectional"))
      (node (ref "IC2") (pin "6") (pinfunction "VS_6") (pintype "bidirectional"))
      (node (ref "IC3") (pin "1") (pinfunction "A1_1") (pintype "bidirectional"))
      (node (ref "IC3") (pin "2") (pinfunction "A0_2") (pintype "bidirectional"))
      (node (ref "IC3") (pin "6") (pinfunction "VS_6") (pintype "bidirectional"))
      (node (ref "IC6") (pin "1") (pinfunction "A1_1") (pintype "bidirectional"))
      (node (ref "IC6") (pin "6") (pinfunction "VS_6") (pintype "bidirectional"))
      (node (ref "IC9") (pin "6") (pinfunction "VS_6") (pintype "bidirectional"))
      (node (ref "J2") (pin "2") (pinfunction "2_2") (pintype "bidirectional"))
      (node (ref "J3") (pin "2") (pinfunction "2_2") (pintype "bidirectional"))
      (node (ref "J7") (pin "2") (pinfunction "2_2") (pintype "bidirectional"))
      (node (ref "J8") (pin "2") (pinfunction "2_2") (pintype "bidirectional"))
      (node (ref "MOD1") (pin "P$1") (pinfunction "VIN_P$1") (pintype "bidirectional"))
      (node (ref "MOD2") (pin "P$1") (pinfunction "VIN_P$1") (pintype "bidirectional"))
      (node (ref "MOD4") (pin "P$1") (pinfunction "VCC_P$1") (pintype "bidirectional"))
      (node (ref "PROG") (pin "4") (pinfunction "4_4") (pintype "bidirectional"))
      (node (ref "R17") (pin "2") (pinfunction "2_2") (pintype "passive"))
      (node (ref "R3") (pin "2") (pinfunction "2_2") (pintype "passive"))
      (node (ref "R8") (pin "2") (pinfunction "2_2") (pintype "passive"))
      (node (ref "SV1") (pin "1") (pinfunction "1_1") (pintype "passive"))
      (node (ref "SV2") (pin "1") (pinfunction "1_1") (pintype "passive"))
    )
    (net (code "2") (name "+5V") (class "Default")
      (node (ref "C3") (pin "1") (pinfunction "1_1") (pintype "passive"))
      (node (ref "IC5") (pin "1") (pinfunction "VIN_1") (pintype "bidirectional"))
      (node (ref "J2") (pin "1") (pinfunction "1_1") (pintype "bidirectional"))
      (node (ref "J3") (pin "1") (pinfunction "1_1") (pintype "bidirectional"))
      (node (ref "J4") (pin "1") (pinfunction "1_1") (pintype "bidirectional"))
      (node (ref "J5") (pin "1") (pinfunction "1_1") (pintype "bidirectional"))
      (node (ref "J6") (pin "1") (pinfunction "1_1") (pintype "bidirectional"))
      (node (ref "J7") (pin "1") (pinfunction "1_1") (pintype "bidirectional"))
      (node (ref "J8") (pin "1") (pinfunction "1_1") (pintype "bidirectional"))
      (node (ref "R5") (pin "2") (pinfunction "2_2") (pintype "passive"))
    )
    (net (code "3") (name "+24V") (class "Default")
      (node (ref "C12") (pin "1") (pinfunction "1_1") (pintype "passive"))
      (node (ref "C14") (pin "1") (pinfunction "1_1") (pintype "passive"))
      (node (ref "IC4") (pin "1") (pinfunction "+VIN_1") (pintype "bidirectional"))
      (node (ref "R10") (pin "2") (pinfunction "2_2") (pintype "bidirectional"))
    )
    (net (code "4") (name "ADC_REGEN_SENS") (class "Default")
      (node (ref "J6") (pin "2") (pinfunction "2_2") (pintype "bidirectional"))
      (node (ref "R25") (pin "1") (pinfunction "1_1") (pintype "passive"))
    )
    (net (code "5") (name "AIN_00") (class "Default")
      (node (ref "C16") (pin "1") (pinfunction "1_1") (pintype "passive"))
      (node (ref "IC8") (pin "20") (pinfunction "PD0_20") (pintype "bidirectional"))
      (node (ref "R11") (pin "2") (pinfunction "2_2") (pintype "passive"))
    )
    (net (code "6") (name "AIN_01") (class "Default")
      (node (ref "C17") (pin "1") (pinfunction "1_1") (pintype "passive"))
      (node (ref "IC8") (pin "21") (pinfunction "PD1_21") (pintype "bidirectional"))
      (node (ref "R12") (pin "2") (pinfunction "2_2") (pintype "passive"))
    )
    (net (code "7") (name "AIN_02") (class "Default")
      (node (ref "C18") (pin "1") (pinfunction "1_1") (pintype "passive"))
      (node (ref "IC8") (pin "22") (pinfunction "PD2_22") (pintype "bidirectional"))
      (node (ref "R13") (pin "2") (pinfunction "2_2") (pintype "passive"))
    )
    (net (code "8") (name "AIN_03") (class "Default")
      (node (ref "C19") (pin "1") (pinfunction "1_1") (pintype "passive"))
      (node (ref "IC8") (pin "23") (pinfunction "PD3_23") (pintype "bidirectional"))
      (node (ref "R14") (pin "2") (pinfunction "2_2") (pintype "passive"))
    )
    (net (code "9") (name "AIN_04") (class "Default")
      (node (ref "C47") (pin "1") (pinfunction "1_1") (pintype "passive"))
      (node (ref "IC8") (pin "24") (pinfunction "PD4_24") (pintype "bidirectional"))
      (node (ref "R18") (pin "2") (pinfunction "2_2") (pintype "passive"))
    )
    (net (code "10") (name "AIN_05") (class "Default")
      (node (ref "C48") (pin "1") (pinfunction "1_1") (pintype "passive"))
      (node (ref "IC8") (pin "25") (pinfunction "PD5_25") (pintype "bidirectional"))
      (node (ref "R19") (pin "2") (pinfunction "2_2") (pintype "passive"))
    )
    (net (code "11") (name "AIN_06") (class "Default")
      (node (ref "C49") (pin "1") (pinfunction "1_1") (pintype "passive"))
      (node (ref "IC8") (pin "26") (pinfunction "PD6_26") (pintype "bidirectional"))
      (node (ref "R25") (pin "2") (pinfunction "2_2") (pintype "passive"))
    )
    (net (code "12") (name "CURR_ALERT_CHRG") (class "Default")
      (node (ref "IC6") (pin "3") (pinfunction "ALERT_3") (pintype "bidirectional"))
      (node (ref "IC8") (pin "4") (pinfunction "PB0_4") (pintype "bidirectional"))
    )
    (net (code "13") (name "CURR_ALERT_M1") (class "Default")
      (node (ref "IC1") (pin "3") (pinfunction "ALERT_3") (pintype "bidirectional"))
      (node (ref "IC8") (pin "11") (pinfunction "PC1_11") (pintype "bidirectional"))
    )
    (net (code "14") (name "CURR_ALERT_M2") (class "Default")
      (node (ref "IC2") (pin "3") (pinfunction "ALERT_3") (pintype "bidirectional"))
      (node (ref "IC8") (pin "10") (pinfunction "PC0_10") (pintype "bidirectional"))
    )
    (net (code "15") (name "CURR_ALERT_M3") (class "Default")
      (node (ref "IC8") (pin "9") (pinfunction "PB5_9") (pintype "bidirectional"))
      (node (ref "IC9") (pin "3") (pinfunction "ALERT_3") (pintype "bidirectional"))
    )
    (net (code "16") (name "CURR_ALERT_M4") (class "Default")
      (node (ref "IC10") (pin "3") (pinfunction "ALERT_3") (pintype "bidirectional"))
      (node (ref "IC8") (pin "8") (pinfunction "PB4_8") (pintype "bidirectional"))
    )
    (net (code "17") (name "CURR_ALERT_M5") (class "Default")
      (node (ref "IC11") (pin "3") (pinfunction "ALERT_3") (pintype "bidirectional"))
      (node (ref "IC8") (pin "5") (pinfunction "PB1_5") (pintype "bidirectional"))
    )
    (net (code "18") (name "CURR_ALERT_SYS") (class "Default")
      (node (ref "IC3") (pin "3") (pinfunction "ALERT_3") (pintype "bidirectional"))
      (node (ref "IC8") (pin "3") (pinfunction "PA7_3") (pintype "bidirectional"))
    )
    (net (code "19") (name "GND") (class "Default")
      (node (ref "C1") (pin "2") (pinfunction "2_2") (pintype "passive"))
      (node (ref "C10") (pin "2") (pinfunction "2_2") (pintype "passive"))
      (node (ref "C11") (pin "2") (pinfunction "2_2") (pintype "passive"))
      (node (ref "C16") (pin "2") (pinfunction "2_2") (pintype "passive"))
      (node (ref "C17") (pin "2") (pinfunction "2_2") (pintype "passive"))
      (node (ref "C18") (pin "2") (pinfunction "2_2") (pintype "passive"))
      (node (ref "C19") (pin "2") (pinfunction "2_2") (pintype "passive"))
      (node (ref "C2") (pin "2") (pinfunction "2_2") (pintype "passive"))
      (node (ref "C22") (pin "2") (pinfunction "2_2") (pintype "passive"))
      (node (ref "C23") (pin "2") (pinfunction "2_2") (pintype "passive"))
      (node (ref "C24") (pin "2") (pinfunction "2_2") (pintype "passive"))
      (node (ref "C3") (pin "2") (pinfunction "2_2") (pintype "passive"))
      (node (ref "C38") (pin "2") (pinfunction "2_2") (pintype "passive"))
      (node (ref "C4") (pin "2") (pinfunction "2_2") (pintype "passive"))
      (node (ref "C47") (pin "2") (pinfunction "2_2") (pintype "passive"))
      (node (ref "C48") (pin "2") (pinfunction "2_2") (pintype "passive"))
      (node (ref "C49") (pin "2") (pinfunction "2_2") (pintype "passive"))
      (node (ref "C5") (pin "2") (pinfunction "2_2") (pintype "passive"))
      (node (ref "C6") (pin "2") (pinfunction "2_2") (pintype "passive"))
      (node (ref "C7") (pin "2") (pinfunction "2_2") (pintype "passive"))
      (node (ref "C8") (pin "2") (pinfunction "2_2") (pintype "passive"))
      (node (ref "C9") (pin "2") (pinfunction "2_2") (pintype "passive"))
      (node (ref "GPS") (pin "3") (pinfunction "3_3") (pintype "passive"))
      (node (ref "IC1") (pin "1") (pinfunction "A1_1") (pintype "bidirectional"))
      (node (ref "IC1") (pin "2") (pinfunction "A0_2") (pintype "bidirectional"))
      (node (ref "IC1") (pin "7") (pinfunction "GND_7") (pintype "bidirectional"))
      (node (ref "IC10") (pin "1") (pinfunction "A1_1") (pintype "bidirectional"))
      (node (ref "IC10") (pin "7") (pinfunction "GND_7") (pintype "bidirectional"))
      (node (ref "IC11") (pin "2") (pinfunction "A0_2") (pintype "bidirectional"))
      (node (ref "IC11") (pin "7") (pinfunction "GND_7") (pintype "bidirectional"))
      (node (ref "IC13") (pin "14") (pinfunction "VSS_14") (pintype "bidirectional"))
      (node (ref "IC2") (pin "1") (pinfunction "A1_1") (pintype "bidirectional"))
      (node (ref "IC2") (pin "7") (pinfunction "GND_7") (pintype "bidirectional"))
      (node (ref "IC3") (pin "7") (pinfunction "GND_7") (pintype "bidirectional"))
      (node (ref "IC5") (pin "2") (pinfunction "GND_2") (pintype "bidirectional"))
      (node (ref "IC5") (pin "4") (pinfunction "GND._4") (pintype "bidirectional"))
      (node (ref "IC6") (pin "7") (pinfunction "GND_7") (pintype "bidirectional"))
      (node (ref "IC9") (pin "1") (pinfunction "A1_1") (pintype "bidirectional"))
      (node (ref "IC9") (pin "7") (pinfunction "GND_7") (pintype "bidirectional"))
      (node (ref "J2") (pin "6") (pinfunction "6_6") (pintype "bidirectional"))
      (node (ref "J3") (pin "6") (pinfunction "6_6") (pintype "bidirectional"))
      (node (ref "J4") (pin "3") (pinfunction "3_3") (pintype "bidirectional"))
      (node (ref "J5") (pin "3") (pinfunction "3_3") (pintype "bidirectional"))
      (node (ref "J6") (pin "3") (pinfunction "3_3") (pintype "bidirectional"))
      (node (ref "J7") (pin "5") (pinfunction "5_5") (pintype "bidirectional"))
      (node (ref "J8") (pin "5") (pinfunction "5_5") (pintype "bidirectional"))
      (node (ref "MOD1") (pin "P$3") (pinfunction "GND_P$3") (pintype "bidirectional"))
      (node (ref "MOD2") (pin "P$3") (pinfunction "GND_P$3") (pintype "bidirectional"))
      (node (ref "MOD4") (pin "P$2") (pinfunction "GND_P$2") (pintype "bidirectional"))
      (node (ref "PROG") (pin "2") (pinfunction "2_2") (pintype "bidirectional"))
      (node (ref "PROG") (pin "9") (pinfunction "9_9") (pintype "bidirectional"))
      (node (ref "SJ1") (pin "2") (pinfunction "2_2") (pintype "passive"))
      (node (ref "SV1") (pin "10") (pinfunction "10_10") (pintype "passive"))
      (node (ref "SV2") (pin "10") (pinfunction "10_10") (pintype "passive"))
    )
    (net (code "20") (name "GNDA") (class "Default")
      (node (ref "BATT") (pin "2") (pinfunction "K_2") (pintype "passive"))
      (node (ref "C12") (pin "2") (pinfunction "2_2") (pintype "passive"))
      (node (ref "C13") (pin "2") (pinfunction "2_2") (pintype "passive"))
      (node (ref "C14") (pin "2") (pinfunction "2_2") (pintype "passive"))
      (node (ref "C15") (pin "2") (pinfunction "2_2") (pintype "passive"))
      (node (ref "IC4") (pin "2") (pinfunction "GND_2") (pintype "bidirectional"))
      (node (ref "M1") (pin "2") (pinfunction "K_2") (pintype "passive"))
      (node (ref "M2") (pin "2") (pinfunction "K_2") (pintype "passive"))
      (node (ref "M3") (pin "2") (pinfunction "K_2") (pintype "passive"))
      (node (ref "M4") (pin "2") (pinfunction "K_2") (pintype "passive"))
      (node (ref "M5") (pin "2") (pinfunction "K_2") (pintype "passive"))
      (node (ref "SJ1") (pin "1") (pinfunction "1_1") (pintype "passive"))
      (node (ref "X1") (pin "2") (pinfunction "K_2") (pintype "passive"))
    )
    (net (code "21") (name "I2C_0_SCL") (class "Default")
      (node (ref "IC8") (pin "47") (pinfunction "PA3_47") (pintype "bidirectional"))
      (node (ref "J7") (pin "3") (pinfunction "3_3") (pintype "bidirectional"))
      (node (ref "J8") (pin "3") (pinfunction "3_3") (pintype "bidirectional"))
      (node (ref "MOD1") (pin "P$4") (pinfunction "SCL_P$4") (pintype "bidirectional"))
      (node (ref "MOD2") (pin "P$4") (pinfunction "SCK_P$4") (pintype "bidirectional"))
      (node (ref "MOD4") (pin "P$3") (pinfunction "SCK/SCK_P$3") (pintype "bidirectional"))
    )
    (net (code "22") (name "I2C_0_SDA") (class "Default")
      (node (ref "IC8") (pin "46") (pinfunction "PA2_46") (pintype "bidirectional"))
      (node (ref "J7") (pin "4") (pinfunction "4_4") (pintype "bidirectional"))
      (node (ref "J8") (pin "4") (pinfunction "4_4") (pintype "bidirectional"))
      (node (ref "MOD1") (pin "P$5") (pinfunction "SDA_P$5") (pintype "bidirectional"))
      (node (ref "MOD2") (pin "P$6") (pinfunction "SDI/SDA_P$6") (pintype "bidirectional"))
      (node (ref "MOD4") (pin "P$4") (pinfunction "SDA/SDI/SDO_P$4") (pintype "bidirectional"))
    )
    (net (code "23") (name "I2C_1_SCL") (class "Default")
      (node (ref "IC1") (pin "5") (pinfunction "SCL_5") (pintype "bidirectional"))
      (node (ref "IC10") (pin "2") (pinfunction "A0_2") (pintype "bidirectional"))
      (node (ref "IC10") (pin "5") (pinfunction "SCL_5") (pintype "bidirectional"))
      (node (ref "IC11") (pin "5") (pinfunction "SCL_5") (pintype "bidirectional"))
      (node (ref "IC13") (pin "26") (pinfunction "SCL_26") (pintype "bidirectional"))
      (node (ref "IC2") (pin "5") (pinfunction "SCL_5") (pintype "bidirectional"))
      (node (ref "IC3") (pin "5") (pinfunction "SCL_5") (pintype "bidirectional"))
      (node (ref "IC6") (pin "5") (pinfunction "SCL_5") (pintype "bidirectional"))
      (node (ref "IC8") (pin "7") (pinfunction "PB3_7") (pintype "bidirectional"))
      (node (ref "IC9") (pin "5") (pinfunction "SCL_5") (pintype "bidirectional"))
    )
    (net (code "24") (name "I2C_1_SDA") (class "Default")
      (node (ref "IC1") (pin "4") (pinfunction "SDA_4") (pintype "bidirectional"))
      (node (ref "IC10") (pin "4") (pinfunction "SDA_4") (pintype "bidirectional"))
      (node (ref "IC11") (pin "4") (pinfunction "SDA_4") (pintype "bidirectional"))
      (node (ref "IC13") (pin "27") (pinfunction "SDA_27") (pintype "bidirectional"))
      (node (ref "IC2") (pin "4") (pinfunction "SDA_4") (pintype "bidirectional"))
      (node (ref "IC3") (pin "4") (pinfunction "SDA_4") (pintype "bidirectional"))
      (node (ref "IC6") (pin "2") (pinfunction "A0_2") (pintype "bidirectional"))
      (node (ref "IC6") (pin "4") (pinfunction "SDA_4") (pintype "bidirectional"))
      (node (ref "IC8") (pin "6") (pinfunction "PB2_6") (pintype "bidirectional"))
      (node (ref "IC9") (pin "2") (pinfunction "A0_2") (pintype "bidirectional"))
      (node (ref "IC9") (pin "4") (pinfunction "SDA_4") (pintype "bidirectional"))
    )
    (net (code "25") (name "Net-(BATTA-K)") (class "Default")
      (node (ref "BATT") (pin "1") (pinfunction "K_1") (pintype "passive"))
      (node (ref "R6") (pin "2") (pinfunction "2_2") (pintype "bidirectional"))
    )
    (net (code "26") (name "Net-(IC1-IN+)") (class "Default")
      (node (ref "IC1") (pin "10") (pinfunction "IN+_10") (pintype "bidirectional"))
      (node (ref "R1") (pin "3") (pinfunction "3_3") (pintype "bidirectional"))
    )
    (net (code "27") (name "Net-(IC1-IN-)") (class "Default")
      (node (ref "IC1") (pin "9") (pinfunction "IN-_9") (pintype "bidirectional"))
      (node (ref "R1") (pin "4") (pinfunction "4_4") (pintype "bidirectional"))
    )
    (net (code "28") (name "Net-(IC1-VBUS)") (class "Default")
      (node (ref "IC1") (pin "8") (pinfunction "VBUS_8") (pintype "bidirectional"))
      (node (ref "IC10") (pin "8") (pinfunction "VBUS_8") (pintype "bidirectional"))
      (node (ref "IC11") (pin "8") (pinfunction "VBUS_8") (pintype "bidirectional"))
      (node (ref "IC2") (pin "8") (pinfunction "VBUS_8") (pintype "bidirectional"))
      (node (ref "IC3") (pin "8") (pinfunction "VBUS_8") (pintype "bidirectional"))
      (node (ref "IC6") (pin "8") (pinfunction "VBUS_8") (pintype "bidirectional"))
      (node (ref "IC9") (pin "8") (pinfunction "VBUS_8") (pintype "bidirectional"))
      (node (ref "R1") (pin "1") (pinfunction "1_1") (pintype "bidirectional"))
      (node (ref "R10") (pin "1") (pinfunction "1_1") (pintype "bidirectional"))
      (node (ref "R15") (pin "1") (pinfunction "1_1") (pintype "bidirectional"))
      (node (ref "R16") (pin "1") (pinfunction "1_1") (pintype "bidirectional"))
      (node (ref "R2") (pin "1") (pinfunction "1_1") (pintype "bidirectional"))
      (node (ref "R4") (pin "1") (pinfunction "1_1") (pintype "bidirectional"))
      (node (ref "R6") (pin "1") (pinfunction "1_1") (pintype "bidirectional"))
      (node (ref "X1") (pin "1") (pinfunction "K_1") (pintype "passive"))
    )
    (net (code "29") (name "Net-(IC2-IN+)") (class "Default")
      (node (ref "IC2") (pin "10") (pinfunction "IN+_10") (pintype "bidirectional"))
      (node (ref "R2") (pin "3") (pinfunction "3_3") (pintype "bidirectional"))
    )
    (net (code "30") (name "Net-(IC2-IN-)") (class "Default")
      (node (ref "IC2") (pin "9") (pinfunction "IN-_9") (pintype "bidirectional"))
      (node (ref "R2") (pin "4") (pinfunction "4_4") (pintype "bidirectional"))
    )
    (net (code "31") (name "Net-(IC3-IN+)") (class "Default")
      (node (ref "IC3") (pin "10") (pinfunction "IN+_10") (pintype "bidirectional"))
      (node (ref "R10") (pin "3") (pinfunction "3_3") (pintype "bidirectional"))
    )
    (net (code "32") (name "Net-(IC3-IN-)") (class "Default")
      (node (ref "IC3") (pin "9") (pinfunction "IN-_9") (pintype "bidirectional"))
      (node (ref "R10") (pin "4") (pinfunction "4_4") (pintype "bidirectional"))
    )
    (net (code "33") (name "Net-(IC4-+VOUT)") (class "Default")
      (node (ref "C13") (pin "1") (pinfunction "1_1") (pintype "passive"))
      (node (ref "C15") (pin "1") (pinfunction "1_1") (pintype "passive"))
      (node (ref "IC4") (pin "3") (pinfunction "+VOUT_3") (pintype "bidirectional"))
      (node (ref "R5") (pin "1") (pinfunction "1_1") (pintype "passive"))
    )
    (net (code "34") (name "Net-(IC5-OUT)") (class "Default")
      (node (ref "C11") (pin "1") (pinfunction "1_1") (pintype "passive"))
      (node (ref "C4") (pin "1") (pinfunction "1_1") (pintype "passive"))
      (node (ref "IC5") (pin "3") (pinfunction "OUT_3") (pintype "bidirectional"))
      (node (ref "R3") (pin "1") (pinfunction "1_1") (pintype "passive"))
    )
    (net (code "35") (name "Net-(IC6-IN+)") (class "Default")
      (node (ref "IC6") (pin "10") (pinfunction "IN+_10") (pintype "bidirectional"))
      (node (ref "R6") (pin "3") (pinfunction "3_3") (pintype "bidirectional"))
    )
    (net (code "36") (name "Net-(IC6-IN-)") (class "Default")
      (node (ref "IC6") (pin "9") (pinfunction "IN-_9") (pintype "bidirectional"))
      (node (ref "R6") (pin "4") (pinfunction "4_4") (pintype "bidirectional"))
    )
    (net (code "37") (name "Net-(IC9-IN+)") (class "Default")
      (node (ref "IC9") (pin "10") (pinfunction "IN+_10") (pintype "bidirectional"))
      (node (ref "R4") (pin "3") (pinfunction "3_3") (pintype "bidirectional"))
    )
    (net (code "38") (name "Net-(IC9-IN-)") (class "Default")
      (node (ref "IC9") (pin "9") (pinfunction "IN-_9") (pintype "bidirectional"))
      (node (ref "R4") (pin "4") (pinfunction "4_4") (pintype "bidirectional"))
    )
    (net (code "39") (name "Net-(IC10-IN+)") (class "Default")
      (node (ref "IC10") (pin "10") (pinfunction "IN+_10") (pintype "bidirectional"))
      (node (ref "R15") (pin "3") (pinfunction "3_3") (pintype "bidirectional"))
    )
    (net (code "40") (name "Net-(IC10-IN-)") (class "Default")
      (node (ref "IC10") (pin "9") (pinfunction "IN-_9") (pintype "bidirectional"))
      (node (ref "R15") (pin "4") (pinfunction "4_4") (pintype "bidirectional"))
    )
    (net (code "41") (name "Net-(IC11-IN+)") (class "Default")
      (node (ref "IC11") (pin "10") (pinfunction "IN+_10") (pintype "bidirectional"))
      (node (ref "R16") (pin "3") (pinfunction "3_3") (pintype "bidirectional"))
    )
    (net (code "42") (name "Net-(IC11-IN-)") (class "Default")
      (node (ref "IC11") (pin "9") (pinfunction "IN-_9") (pintype "bidirectional"))
      (node (ref "R16") (pin "4") (pinfunction "4_4") (pintype "bidirectional"))
    )
    (net (code "43") (name "Net-(IC13-LED0)") (class "Default")
      (node (ref "IC13") (pin "6") (pinfunction "LED0_6") (pintype "bidirectional"))
      (node (ref "SV1") (pin "2") (pinfunction "2_2") (pintype "passive"))
    )
    (net (code "44") (name "Net-(IC13-LED1)") (class "Default")
      (node (ref "IC13") (pin "7") (pinfunction "LED1_7") (pintype "bidirectional"))
      (node (ref "SV1") (pin "3") (pinfunction "3_3") (pintype "passive"))
    )
    (net (code "45") (name "Net-(IC13-LED2)") (class "Default")
      (node (ref "IC13") (pin "8") (pinfunction "LED2_8") (pintype "bidirectional"))
      (node (ref "SV1") (pin "4") (pinfunction "4_4") (pintype "passive"))
    )
    (net (code "46") (name "Net-(IC13-LED3)") (class "Default")
      (node (ref "IC13") (pin "9") (pinfunction "LED3_9") (pintype "bidirectional"))
      (node (ref "SV1") (pin "5") (pinfunction "5_5") (pintype "passive"))
    )
    (net (code "47") (name "Net-(IC13-LED4)") (class "Default")
      (node (ref "IC13") (pin "10") (pinfunction "LED4_10") (pintype "bidirectional"))
      (node (ref "SV1") (pin "6") (pinfunction "6_6") (pintype "passive"))
    )
    (net (code "48") (name "Net-(IC13-LED5)") (class "Default")
      (node (ref "IC13") (pin "11") (pinfunction "LED5_11") (pintype "bidirectional"))
      (node (ref "SV1") (pin "7") (pinfunction "7_7") (pintype "passive"))
    )
    (net (code "49") (name "Net-(IC13-LED6)") (class "Default")
      (node (ref "IC13") (pin "12") (pinfunction "LED6_12") (pintype "bidirectional"))
      (node (ref "SV1") (pin "8") (pinfunction "8_8") (pintype "passive"))
    )
    (net (code "50") (name "Net-(IC13-LED7)") (class "Default")
      (node (ref "IC13") (pin "13") (pinfunction "LED7_13") (pintype "bidirectional"))
      (node (ref "SV1") (pin "9") (pinfunction "9_9") (pintype "passive"))
    )
    (net (code "51") (name "Net-(IC13-LED8)") (class "Default")
      (node (ref "IC13") (pin "15") (pinfunction "LED8_15") (pintype "bidirectional"))
      (node (ref "SV2") (pin "2") (pinfunction "2_2") (pintype "passive"))
    )
    (net (code "52") (name "Net-(IC13-LED9)") (class "Default")
      (node (ref "IC13") (pin "16") (pinfunction "LED9_16") (pintype "bidirectional"))
      (node (ref "SV2") (pin "3") (pinfunction "3_3") (pintype "passive"))
    )
    (net (code "53") (name "Net-(IC13-LED10)") (class "Default")
      (node (ref "IC13") (pin "17") (pinfunction "LED10_17") (pintype "bidirectional"))
      (node (ref "SV2") (pin "4") (pinfunction "4_4") (pintype "passive"))
    )
    (net (code "54") (name "Net-(IC13-LED11)") (class "Default")
      (node (ref "IC13") (pin "18") (pinfunction "LED11_18") (pintype "bidirectional"))
      (node (ref "SV2") (pin "5") (pinfunction "5_5") (pintype "passive"))
    )
    (net (code "55") (name "Net-(IC13-LED12)") (class "Default")
      (node (ref "IC13") (pin "19") (pinfunction "LED12_19") (pintype "bidirectional"))
      (node (ref "SV2") (pin "6") (pinfunction "6_6") (pintype "passive"))
    )
    (net (code "56") (name "Net-(IC13-LED13)") (class "Default")
      (node (ref "IC13") (pin "20") (pinfunction "LED13_20") (pintype "bidirectional"))
      (node (ref "SV2") (pin "7") (pinfunction "7_7") (pintype "passive"))
    )
    (net (code "57") (name "Net-(IC13-LED14)") (class "Default")
      (node (ref "IC13") (pin "21") (pinfunction "LED14_21") (pintype "bidirectional"))
      (node (ref "SV2") (pin "8") (pinfunction "8_8") (pintype "passive"))
    )
    (net (code "58") (name "Net-(IC13-LED15)") (class "Default")
      (node (ref "IC13") (pin "22") (pinfunction "LED15_22") (pintype "bidirectional"))
      (node (ref "SV2") (pin "9") (pinfunction "9_9") (pintype "passive"))
    )
    (net (code "59") (name "Net-(J2-Pad3)") (class "Default")
      (node (ref "J2") (pin "3") (pinfunction "3_3") (pintype "bidirectional"))
      (node (ref "R11") (pin "1") (pinfunction "1_1") (pintype "passive"))
    )
    (net (code "60") (name "Net-(J2-Pad4)") (class "Default")
      (node (ref "J2") (pin "4") (pinfunction "4_4") (pintype "bidirectional"))
      (node (ref "R12") (pin "1") (pinfunction "1_1") (pintype "passive"))
    )
    (net (code "61") (name "Net-(J2-Pad5)") (class "Default")
      (node (ref "J2") (pin "5") (pinfunction "5_5") (pintype "bidirectional"))
      (node (ref "R13") (pin "1") (pinfunction "1_1") (pintype "passive"))
    )
    (net (code "62") (name "Net-(J3-Pad3)") (class "Default")
      (node (ref "J3") (pin "3") (pinfunction "3_3") (pintype "bidirectional"))
      (node (ref "R14") (pin "1") (pinfunction "1_1") (pintype "passive"))
    )
    (net (code "63") (name "Net-(J3-Pad4)") (class "Default")
      (node (ref "J3") (pin "4") (pinfunction "4_4") (pintype "bidirectional"))
      (node (ref "R18") (pin "1") (pinfunction "1_1") (pintype "passive"))
    )
    (net (code "64") (name "Net-(J3-Pad5)") (class "Default")
      (node (ref "J3") (pin "5") (pinfunction "5_5") (pintype "bidirectional"))
      (node (ref "R19") (pin "1") (pinfunction "1_1") (pintype "passive"))
    )
    (net (code "65") (name "Net-(M1A-K)") (class "Default")
      (node (ref "M1") (pin "1") (pinfunction "K_1") (pintype "passive"))
      (node (ref "R1") (pin "2") (pinfunction "2_2") (pintype "bidirectional"))
    )
    (net (code "66") (name "Net-(M2A-K)") (class "Default")
      (node (ref "M2") (pin "1") (pinfunction "K_1") (pintype "passive"))
      (node (ref "R2") (pin "2") (pinfunction "2_2") (pintype "bidirectional"))
    )
    (net (code "67") (name "Net-(M3A-K)") (class "Default")
      (node (ref "M3") (pin "1") (pinfunction "K_1") (pintype "passive"))
      (node (ref "R4") (pin "2") (pinfunction "2_2") (pintype "bidirectional"))
    )
    (net (code "68") (name "Net-(M4A-K)") (class "Default")
      (node (ref "M4") (pin "1") (pinfunction "K_1") (pintype "passive"))
      (node (ref "R15") (pin "2") (pinfunction "2_2") (pintype "bidirectional"))
    )
    (net (code "69") (name "Net-(M5A-K)") (class "Default")
      (node (ref "M5") (pin "1") (pinfunction "K_1") (pintype "passive"))
      (node (ref "R16") (pin "2") (pinfunction "2_2") (pintype "bidirectional"))
    )
    (net (code "70") (name "Net-(PROG-Pad3)") (class "Default")
      (node (ref "PROG") (pin "3") (pinfunction "3_3") (pintype "bidirectional"))
      (node (ref "R8") (pin "1") (pinfunction "1_1") (pintype "passive"))
    )
    (net (code "71") (name "Net-(PROG-Pad6)") (class "Default")
      (node (ref "PROG") (pin "6") (pinfunction "6_6") (pintype "bidirectional"))
      (node (ref "R7") (pin "2") (pinfunction "2_2") (pintype "passive"))
    )
    (net (code "72") (name "PWM_PCA9685_OE") (class "Default")
      (node (ref "IC13") (pin "23") (pinfunction "~{OE}_23") (pintype "bidirectional"))
      (node (ref "IC8") (pin "12") (pinfunction "PC2_12") (pintype "bidirectional"))
    )
    (net (code "73") (name "SPI_0_CS") (class "Default")
      (node (ref "IC8") (pin "33") (pinfunction "PE3_33") (pintype "bidirectional"))
    )
    (net (code "74") (name "SPI_0_MISO") (class "Default")
      (node (ref "IC8") (pin "31") (pinfunction "PE1_31") (pintype "bidirectional"))
    )
    (net (code "75") (name "SPI_0_MOSI") (class "Default")
      (node (ref "IC8") (pin "30") (pinfunction "PE0_30") (pintype "bidirectional"))
    )
    (net (code "76") (name "SPI_0_SCK") (class "Default")
      (node (ref "IC8") (pin "32") (pinfunction "PE2_32") (pintype "bidirectional"))
    )
    (net (code "77") (name "UART_0_RXD") (class "Default")
      (node (ref "GPS") (pin "2") (pinfunction "2_2") (pintype "passive"))
      (node (ref "IC8") (pin "45") (pinfunction "PA1(XTALHF2)_45") (pintype "bidirectional"))
    )
    (net (code "78") (name "UART_0_TXD") (class "Default")
      (node (ref "GPS") (pin "1") (pinfunction "1_1") (pintype "passive"))
      (node (ref "IC8") (pin "44") (pinfunction "PA0(XTALHF1)_44") (pintype "bidirectional"))
    )
    (net (code "79") (name "UART_2_RXD") (class "Default")
      (node (ref "IC8") (pin "39") (pinfunction "PF5_39") (pintype "bidirectional"))
    )
    (net (code "80") (name "UART_2_TXD") (class "Default")
      (node (ref "IC8") (pin "38") (pinfunction "PF4_38") (pintype "bidirectional"))
    )
    (net (code "81") (name "UPDI") (class "Default")
      (node (ref "IC8") (pin "41") (pinfunction "UPDI_41") (pintype "bidirectional"))
    )
    (net (code "82") (name "WS2812B_1_OUT") (class "Default")
      (node (ref "J4") (pin "2") (pinfunction "2_2") (pintype "bidirectional"))
    )
    (net (code "83") (name "WS2812B_2_OUT") (class "Default")
      (node (ref "J5") (pin "2") (pinfunction "2_2") (pintype "bidirectional"))
    )
    (net (code "84") (name "unconnected-(GPS-Pad5)") (class "Default")
      (node (ref "GPS") (pin "5") (pinfunction "5_5") (pintype "passive"))
    )
    (net (code "85") (name "unconnected-(GPS-Pad6)") (class "Default")
      (node (ref "GPS") (pin "6") (pinfunction "6_6") (pintype "passive"))
    )
    (net (code "86") (name "unconnected-(GPS-Pad7)") (class "Default")
      (node (ref "GPS") (pin "7") (pinfunction "7_7") (pintype "passive"))
    )
    (net (code "87") (name "unconnected-(GPS-Pad8)") (class "Default")
      (node (ref "GPS") (pin "8") (pinfunction "8_8") (pintype "passive"))
    )
    (net (code "88") (name "unconnected-(IC7-3V3-Pad2)") (class "Default")
      (node (ref "IC7") (pin "2") (pinfunction "3V3_2") (pintype "bidirectional"))
    )
    (net (code "89") (name "unconnected-(IC7-CLK-Pad20)") (class "Default")
      (node (ref "IC7") (pin "20") (pinfunction "CLK_20") (pintype "bidirectional"))
    )
    (net (code "90") (name "unconnected-(IC7-CMD-Pad19)") (class "Default")
      (node (ref "IC7") (pin "19") (pinfunction "CMD_19") (pintype "bidirectional"))
    )
    (net (code "91") (name "unconnected-(IC7-EN-Pad3)") (class "Default")
      (node (ref "IC7") (pin "3") (pinfunction "EN_3") (pintype "bidirectional"))
    )
    (net (code "92") (name "unconnected-(IC7-GND_1-Pad1)") (class "Default")
      (node (ref "IC7") (pin "1") (pinfunction "GND_1_1") (pintype "bidirectional"))
    )
    (net (code "93") (name "unconnected-(IC7-GND_2-Pad15)") (class "Default")
      (node (ref "IC7") (pin "15") (pinfunction "GND_2_15") (pintype "bidirectional"))
    )
    (net (code "94") (name "unconnected-(IC7-GND_3-Pad38)") (class "Default")
      (node (ref "IC7") (pin "38") (pinfunction "GND_3_38") (pintype "bidirectional"))
    )
    (net (code "95") (name "unconnected-(IC7-GND_4-Pad39)") (class "Default")
      (node (ref "IC7") (pin "39") (pinfunction "GND_4_39") (pintype "bidirectional"))
    )
    (net (code "96") (name "unconnected-(IC7-IO0-Pad25)") (class "Default")
      (node (ref "IC7") (pin "25") (pinfunction "IO0_25") (pintype "bidirectional"))
    )
    (net (code "97") (name "unconnected-(IC7-IO2-Pad24)") (class "Default")
      (node (ref "IC7") (pin "24") (pinfunction "IO2_24") (pintype "bidirectional"))
    )
    (net (code "98") (name "unconnected-(IC7-IO4-Pad26)") (class "Default")
      (node (ref "IC7") (pin "26") (pinfunction "IO4_26") (pintype "bidirectional"))
    )
    (net (code "99") (name "unconnected-(IC7-IO5-Pad29)") (class "Default")
      (node (ref "IC7") (pin "29") (pinfunction "IO5_29") (pintype "bidirectional"))
    )
    (net (code "100") (name "unconnected-(IC7-IO12-Pad14)") (class "Default")
      (node (ref "IC7") (pin "14") (pinfunction "IO12_14") (pintype "bidirectional"))
    )
    (net (code "101") (name "unconnected-(IC7-IO13-Pad16)") (class "Default")
      (node (ref "IC7") (pin "16") (pinfunction "IO13_16") (pintype "bidirectional"))
    )
    (net (code "102") (name "unconnected-(IC7-IO14-Pad13)") (class "Default")
      (node (ref "IC7") (pin "13") (pinfunction "IO14_13") (pintype "bidirectional"))
    )
    (net (code "103") (name "unconnected-(IC7-IO15-Pad23)") (class "Default")
      (node (ref "IC7") (pin "23") (pinfunction "IO15_23") (pintype "bidirectional"))
    )
    (net (code "104") (name "unconnected-(IC7-IO16-Pad27)") (class "Default")
      (node (ref "IC7") (pin "27") (pinfunction "IO16_27") (pintype "bidirectional"))
    )
    (net (code "105") (name "unconnected-(IC7-IO17-Pad28)") (class "Default")
      (node (ref "IC7") (pin "28") (pinfunction "IO17_28") (pintype "bidirectional"))
    )
    (net (code "106") (name "unconnected-(IC7-IO18-Pad30)") (class "Default")
      (node (ref "IC7") (pin "30") (pinfunction "IO18_30") (pintype "bidirectional"))
    )
    (net (code "107") (name "unconnected-(IC7-IO19-Pad31)") (class "Default")
      (node (ref "IC7") (pin "31") (pinfunction "IO19_31") (pintype "bidirectional"))
    )
    (net (code "108") (name "unconnected-(IC7-IO21-Pad33)") (class "Default")
      (node (ref "IC7") (pin "33") (pinfunction "IO21_33") (pintype "bidirectional"))
    )
    (net (code "109") (name "unconnected-(IC7-IO22-Pad36)") (class "Default")
      (node (ref "IC7") (pin "36") (pinfunction "IO22_36") (pintype "bidirectional"))
    )
    (net (code "110") (name "unconnected-(IC7-IO23-Pad37)") (class "Default")
      (node (ref "IC7") (pin "37") (pinfunction "IO23_37") (pintype "bidirectional"))
    )
    (net (code "111") (name "unconnected-(IC7-IO25-Pad10)") (class "Default")
      (node (ref "IC7") (pin "10") (pinfunction "IO25_10") (pintype "bidirectional"))
    )
    (net (code "112") (name "unconnected-(IC7-IO26-Pad11)") (class "Default")
      (node (ref "IC7") (pin "11") (pinfunction "IO26_11") (pintype "bidirectional"))
    )
    (net (code "113") (name "unconnected-(IC7-IO27-Pad12)") (class "Default")
      (node (ref "IC7") (pin "12") (pinfunction "IO27_12") (pintype "bidirectional"))
    )
    (net (code "114") (name "unconnected-(IC7-IO32-Pad8)") (class "Default")
      (node (ref "IC7") (pin "8") (pinfunction "IO32_8") (pintype "bidirectional"))
    )
    (net (code "115") (name "unconnected-(IC7-IO33-Pad9)") (class "Default")
      (node (ref "IC7") (pin "9") (pinfunction "IO33_9") (pintype "bidirectional"))
    )
    (net (code "116") (name "unconnected-(IC7-IO34-Pad6)") (class "Default")
      (node (ref "IC7") (pin "6") (pinfunction "IO34_6") (pintype "bidirectional"))
    )
    (net (code "117") (name "unconnected-(IC7-IO35-Pad7)") (class "Default")
      (node (ref "IC7") (pin "7") (pinfunction "IO35_7") (pintype "bidirectional"))
    )
    (net (code "118") (name "unconnected-(IC7-NC-Pad32)") (class "Default")
      (node (ref "IC7") (pin "32") (pinfunction "NC_32") (pintype "no_connect"))
    )
    (net (code "119") (name "unconnected-(IC7-RXD0-Pad34)") (class "Default")
      (node (ref "IC7") (pin "34") (pinfunction "RXD0_34") (pintype "bidirectional"))
    )
    (net (code "120") (name "unconnected-(IC7-SD0-Pad21)") (class "Default")
      (node (ref "IC7") (pin "21") (pinfunction "SD0_21") (pintype "bidirectional"))
    )
    (net (code "121") (name "unconnected-(IC7-SD1-Pad22)") (class "Default")
      (node (ref "IC7") (pin "22") (pinfunction "SD1_22") (pintype "bidirectional"))
    )
    (net (code "122") (name "unconnected-(IC7-SD2-Pad17)") (class "Default")
      (node (ref "IC7") (pin "17") (pinfunction "SD2_17") (pintype "bidirectional"))
    )
    (net (code "123") (name "unconnected-(IC7-SD3-Pad18)") (class "Default")
      (node (ref "IC7") (pin "18") (pinfunction "SD3_18") (pintype "bidirectional"))
    )
    (net (code "124") (name "unconnected-(IC7-SENSOR_VN-Pad5)") (class "Default")
      (node (ref "IC7") (pin "5") (pinfunction "SENSOR_VN_5") (pintype "bidirectional"))
    )
    (net (code "125") (name "unconnected-(IC7-SENSOR_VP-Pad4)") (class "Default")
      (node (ref "IC7") (pin "4") (pinfunction "SENSOR_VP_4") (pintype "bidirectional"))
    )
    (net (code "126") (name "unconnected-(IC7-TXD0-Pad35)") (class "Default")
      (node (ref "IC7") (pin "35") (pinfunction "TXD0_35") (pintype "bidirectional"))
    )
    (net (code "127") (name "unconnected-(IC8-AVDD-Pad28)") (class "Default")
      (node (ref "IC8") (pin "28") (pinfunction "AVDD_28") (pintype "bidirectional"))
    )
    (net (code "128") (name "unconnected-(IC8-GND_1-Pad15)") (class "Default")
      (node (ref "IC8") (pin "15") (pinfunction "GND_1_15") (pintype "bidirectional"))
    )
    (net (code "129") (name "unconnected-(IC8-GND_2-Pad29)") (class "Default")
      (node (ref "IC8") (pin "29") (pinfunction "GND_2_29") (pintype "bidirectional"))
    )
    (net (code "130") (name "unconnected-(IC8-GND_3-Pad43)") (class "Default")
      (node (ref "IC8") (pin "43") (pinfunction "GND_3_43") (pintype "bidirectional"))
    )
    (net (code "131") (name "unconnected-(IC8-PA4-Pad48)") (class "Default")
      (node (ref "IC8") (pin "48") (pinfunction "PA4_48") (pintype "bidirectional"))
    )
    (net (code "132") (name "unconnected-(IC8-PA5-Pad1)") (class "Default")
      (node (ref "IC8") (pin "1") (pinfunction "PA5_1") (pintype "bidirectional"))
    )
    (net (code "133") (name "unconnected-(IC8-PA6-Pad2)") (class "Default")
      (node (ref "IC8") (pin "2") (pinfunction "PA6_2") (pintype "bidirectional"))
    )
    (net (code "134") (name "unconnected-(IC8-PC3-Pad13)") (class "Default")
      (node (ref "IC8") (pin "13") (pinfunction "PC3_13") (pintype "bidirectional"))
    )
    (net (code "135") (name "unconnected-(IC8-PC4-Pad16)") (class "Default")
      (node (ref "IC8") (pin "16") (pinfunction "PC4_16") (pintype "bidirectional"))
    )
    (net (code "136") (name "unconnected-(IC8-PC5-Pad17)") (class "Default")
      (node (ref "IC8") (pin "17") (pinfunction "PC5_17") (pintype "bidirectional"))
    )
    (net (code "137") (name "unconnected-(IC8-PC6-Pad18)") (class "Default")
      (node (ref "IC8") (pin "18") (pinfunction "PC6_18") (pintype "bidirectional"))
    )
    (net (code "138") (name "unconnected-(IC8-PC7-Pad19)") (class "Default")
      (node (ref "IC8") (pin "19") (pinfunction "PC7_19") (pintype "bidirectional"))
    )
    (net (code "139") (name "unconnected-(IC8-PD7-Pad27)") (class "Default")
      (node (ref "IC8") (pin "27") (pinfunction "PD7_27") (pintype "bidirectional"))
    )
    (net (code "140") (name "unconnected-(IC8-PF0(XTAL32K1)-Pad34)") (class "Default")
      (node (ref "IC8") (pin "34") (pinfunction "PF0(XTAL32K1)_34") (pintype "bidirectional"))
    )
    (net (code "141") (name "unconnected-(IC8-PF1(XTAL32K2)-Pad35)") (class "Default")
      (node (ref "IC8") (pin "35") (pinfunction "PF1(XTAL32K2)_35") (pintype "bidirectional"))
    )
    (net (code "142") (name "unconnected-(IC8-PF2-Pad36)") (class "Default")
      (node (ref "IC8") (pin "36") (pinfunction "PF2_36") (pintype "bidirectional"))
    )
    (net (code "143") (name "unconnected-(IC8-PF3-Pad37)") (class "Default")
      (node (ref "IC8") (pin "37") (pinfunction "PF3_37") (pintype "bidirectional"))
    )
    (net (code "144") (name "unconnected-(IC8-VDD-Pad42)") (class "Default")
      (node (ref "IC8") (pin "42") (pinfunction "VDD_42") (pintype "bidirectional"))
    )
    (net (code "145") (name "unconnected-(IC8-VDDIO2-Pad14)") (class "Default")
      (node (ref "IC8") (pin "14") (pinfunction "VDDIO2_14") (pintype "bidirectional"))
    )
    (net (code "146") (name "unconnected-(IC13-A0-Pad1)") (class "Default")
      (node (ref "IC13") (pin "1") (pinfunction "A0_1") (pintype "bidirectional"))
    )
    (net (code "147") (name "unconnected-(IC13-A1-Pad2)") (class "Default")
      (node (ref "IC13") (pin "2") (pinfunction "A1_2") (pintype "bidirectional"))
    )
    (net (code "148") (name "unconnected-(IC13-A2-Pad3)") (class "Default")
      (node (ref "IC13") (pin "3") (pinfunction "A2_3") (pintype "bidirectional"))
    )
    (net (code "149") (name "unconnected-(IC13-A3-Pad4)") (class "Default")
      (node (ref "IC13") (pin "4") (pinfunction "A3_4") (pintype "bidirectional"))
    )
    (net (code "150") (name "unconnected-(IC13-A4-Pad5)") (class "Default")
      (node (ref "IC13") (pin "5") (pinfunction "A4_5") (pintype "bidirectional"))
    )
    (net (code "151") (name "unconnected-(IC13-A5-Pad24)") (class "Default")
      (node (ref "IC13") (pin "24") (pinfunction "A5_24") (pintype "bidirectional"))
    )
    (net (code "152") (name "unconnected-(IC13-EXTCLK-Pad25)") (class "Default")
      (node (ref "IC13") (pin "25") (pinfunction "EXTCLK_25") (pintype "bidirectional"))
    )
    (net (code "153") (name "unconnected-(MOD1-3V3-PadP$2)") (class "Default")
      (node (ref "MOD1") (pin "P$2") (pinfunction "3V3_P$2") (pintype "bidirectional"))
    )
    (net (code "154") (name "unconnected-(MOD1-INT1-PadP$10)") (class "Default")
      (node (ref "MOD1") (pin "P$10") (pinfunction "INT1_P$10") (pintype "bidirectional"))
    )
    (net (code "155") (name "unconnected-(MOD1-INT2-PadP$9)") (class "Default")
      (node (ref "MOD1") (pin "P$9") (pinfunction "INT2_P$9") (pintype "bidirectional"))
    )
    (net (code "156") (name "unconnected-(MOD1-SA0-PadP$7)") (class "Default")
      (node (ref "MOD1") (pin "P$7") (pinfunction "SA0_P$7") (pintype "bidirectional"))
    )
    (net (code "157") (name "unconnected-(MOD2-3V3-PadP$2)") (class "Default")
      (node (ref "MOD2") (pin "P$2") (pinfunction "3V3_P$2") (pintype "bidirectional"))
    )
    (net (code "158") (name "unconnected-(MOD2-CS-PadP$7)") (class "Default")
      (node (ref "MOD2") (pin "P$7") (pinfunction "CS_P$7") (pintype "bidirectional"))
    )
    (net (code "159") (name "unconnected-(MOD2-SDO-PadP$5)") (class "Default")
      (node (ref "MOD2") (pin "P$5") (pinfunction "SDO_P$5") (pintype "bidirectional"))
    )
    (net (code "160") (name "unconnected-(MOD4-CSB-PadP$6)") (class "Default")
      (node (ref "MOD4") (pin "P$6") (pinfunction "CSB_P$6") (pintype "bidirectional"))
    )
    (net (code "161") (name "unconnected-(MOD4-DRDY-PadP$8)") (class "Default")
      (node (ref "MOD4") (pin "P$8") (pinfunction "DRDY_P$8") (pintype "bidirectional"))
    )
    (net (code "162") (name "unconnected-(MOD4-INT-PadP$9)") (class "Default")
      (node (ref "MOD4") (pin "P$9") (pinfunction "INT_P$9") (pintype "bidirectional"))
    )
    (net (code "163") (name "unconnected-(MOD4-PS-PadP$7)") (class "Default")
      (node (ref "MOD4") (pin "P$7") (pinfunction "PS_P$7") (pintype "bidirectional"))
    )
    (net (code "164") (name "unconnected-(MOD4-SDO-PadP$5)") (class "Default")
      (node (ref "MOD4") (pin "P$5") (pinfunction "SDO_P$5") (pintype "bidirectional"))
    )
    (net (code "165") (name "unconnected-(PROG-Pad1)") (class "Default")
      (node (ref "PROG") (pin "1") (pinfunction "1_1") (pintype "bidirectional"))
    )
    (net (code "166") (name "unconnected-(PROG-Pad5)") (class "Default")
      (node (ref "PROG") (pin "5") (pinfunction "5_5") (pintype "bidirectional"))
    )
    (net (code "167") (name "unconnected-(PROG-Pad7)") (class "Default")
      (node (ref "PROG") (pin "7") (pinfunction "7_7") (pintype "bidirectional"))
    )
    (net (code "168") (name "unconnected-(PROG-Pad8)") (class "Default")
      (node (ref "PROG") (pin "8") (pinfunction "8_8") (pintype "bidirectional"))
    )
    (net (code "169") (name "unconnected-(PROG-Pad10)") (class "Default")
      (node (ref "PROG") (pin "10") (pinfunction "10_10") (pintype "bidirectional"))
    )
    (net (code "170") (name "{slash}RESET") (class "Default")
      (node (ref "C38") (pin "1") (pinfunction "1_1") (pintype "passive"))
      (node (ref "IC8") (pin "40") (pinfunction "PF6_40") (pintype "bidirectional"))
      (node (ref "R17") (pin "1") (pinfunction "1_1") (pintype "passive"))
      (node (ref "R7") (pin "1") (pinfunction "1_1") (pintype "passive"))
    )
  )
)
